# p25rx_display_rev3.net
KiCad netlist of a schematic drawn in EAGLE
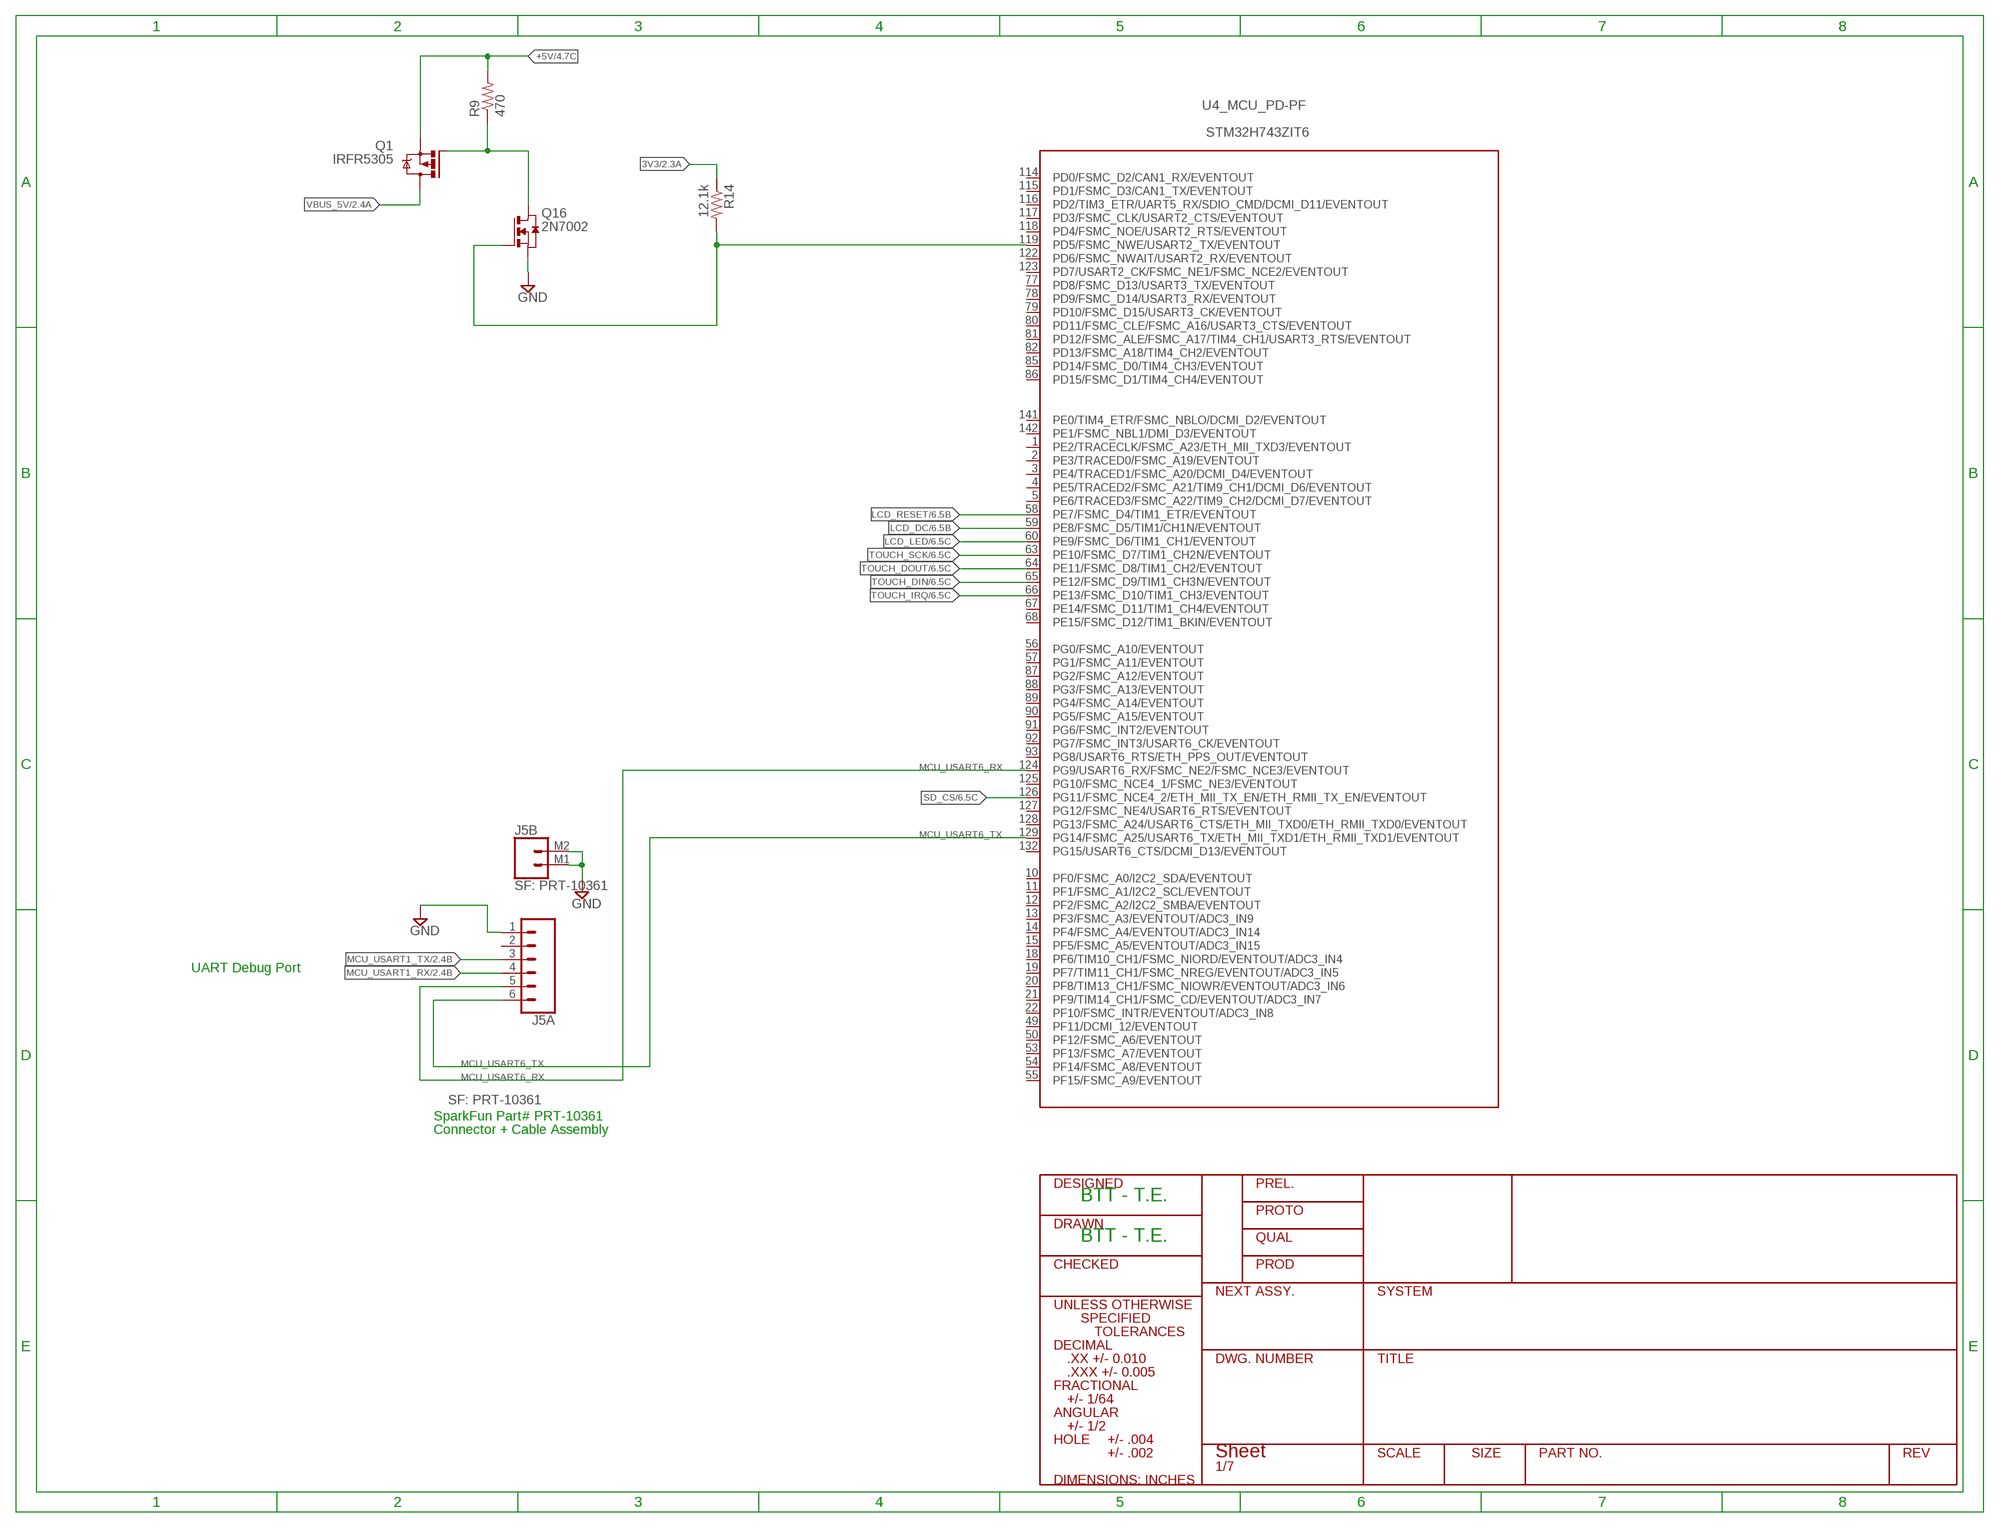
[diagram p0: schematic, sheet 1]
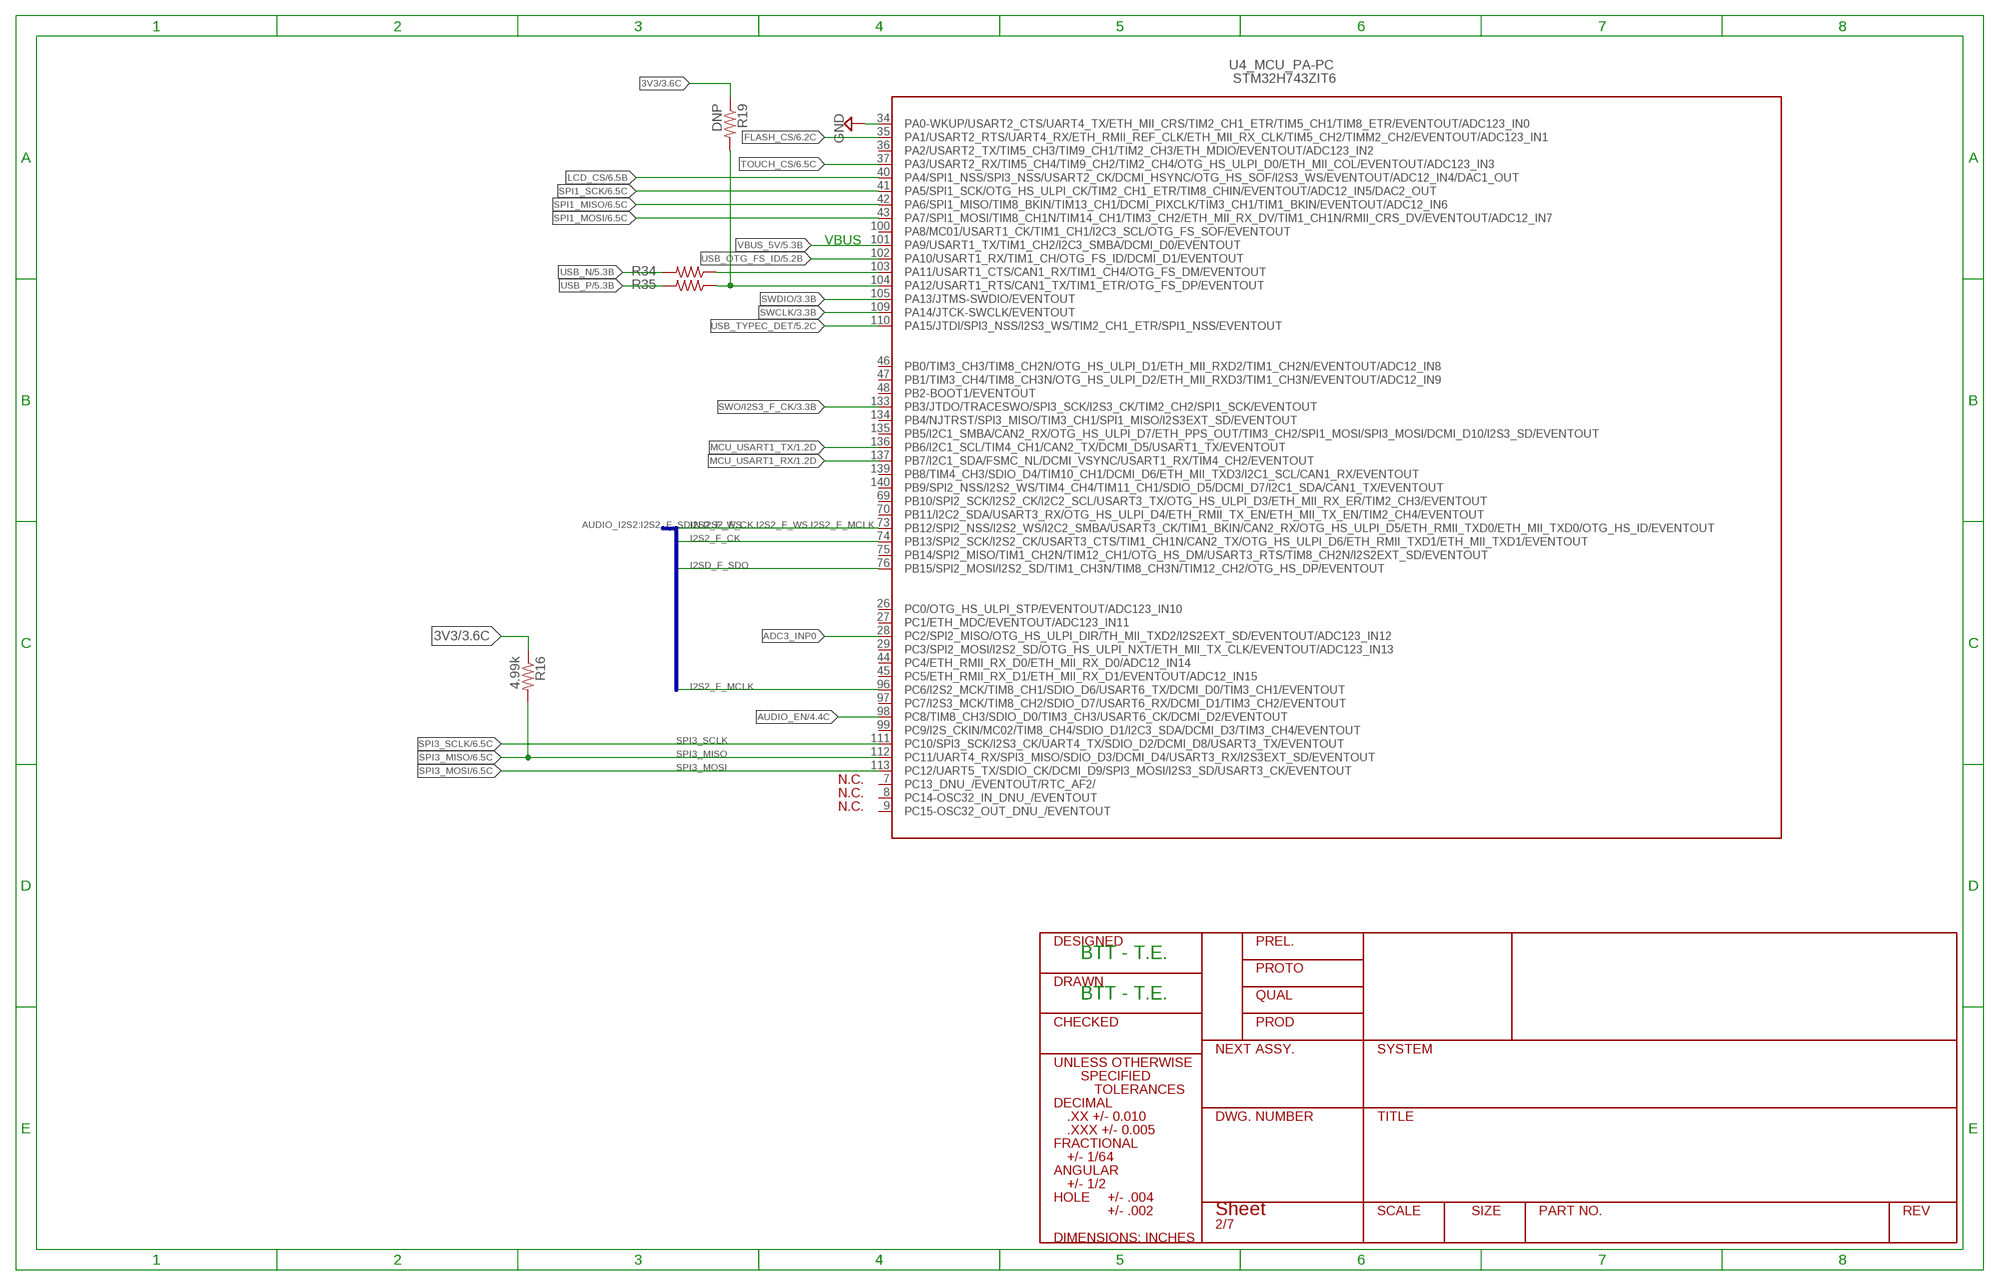
[diagram p1: schematic, sheet 2]
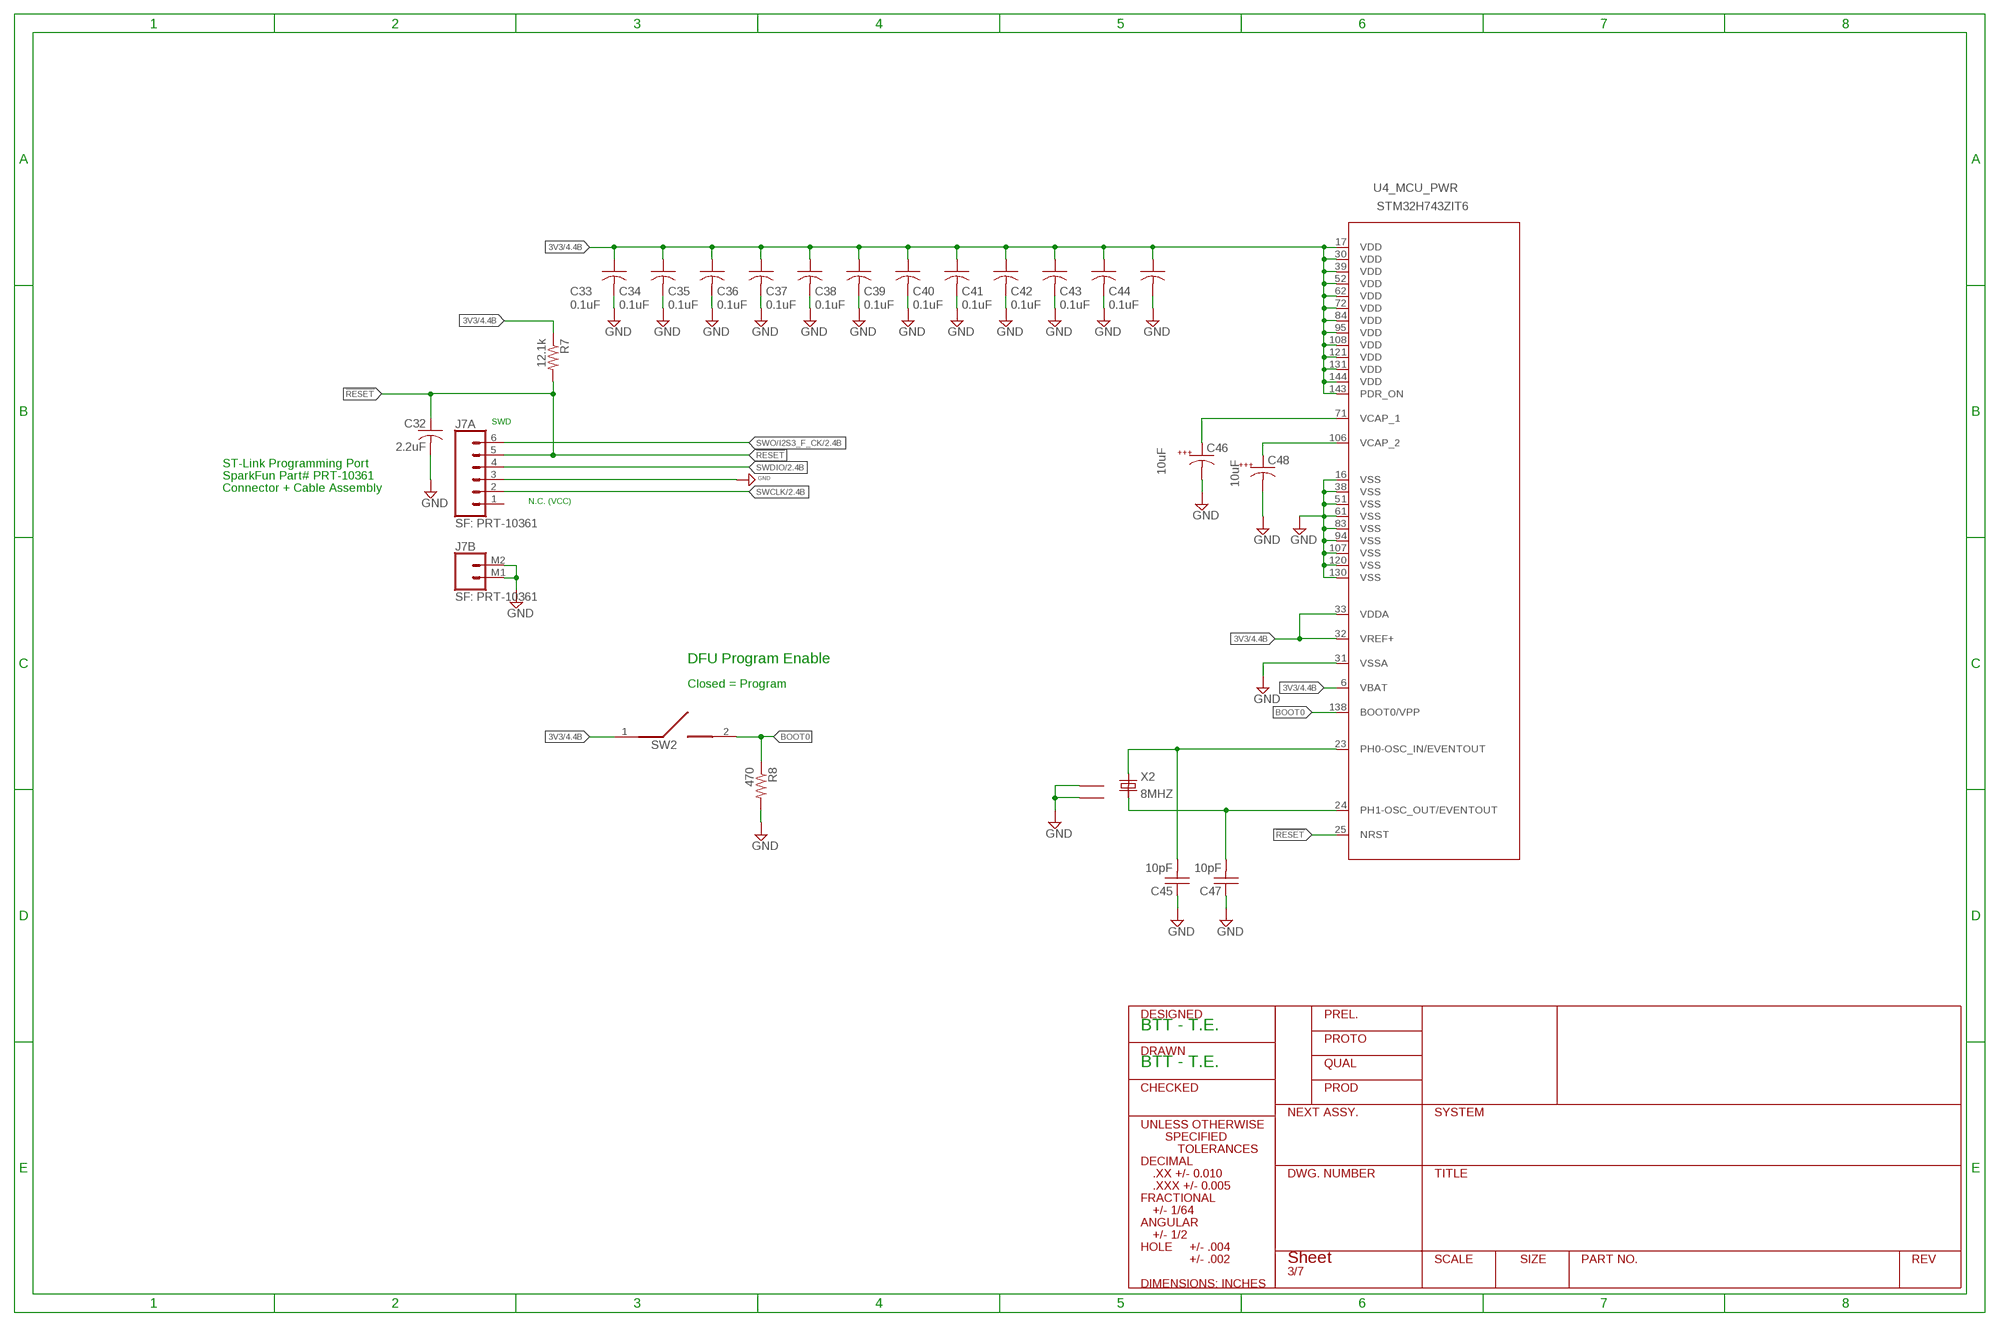
[diagram p2: schematic, sheet 3]
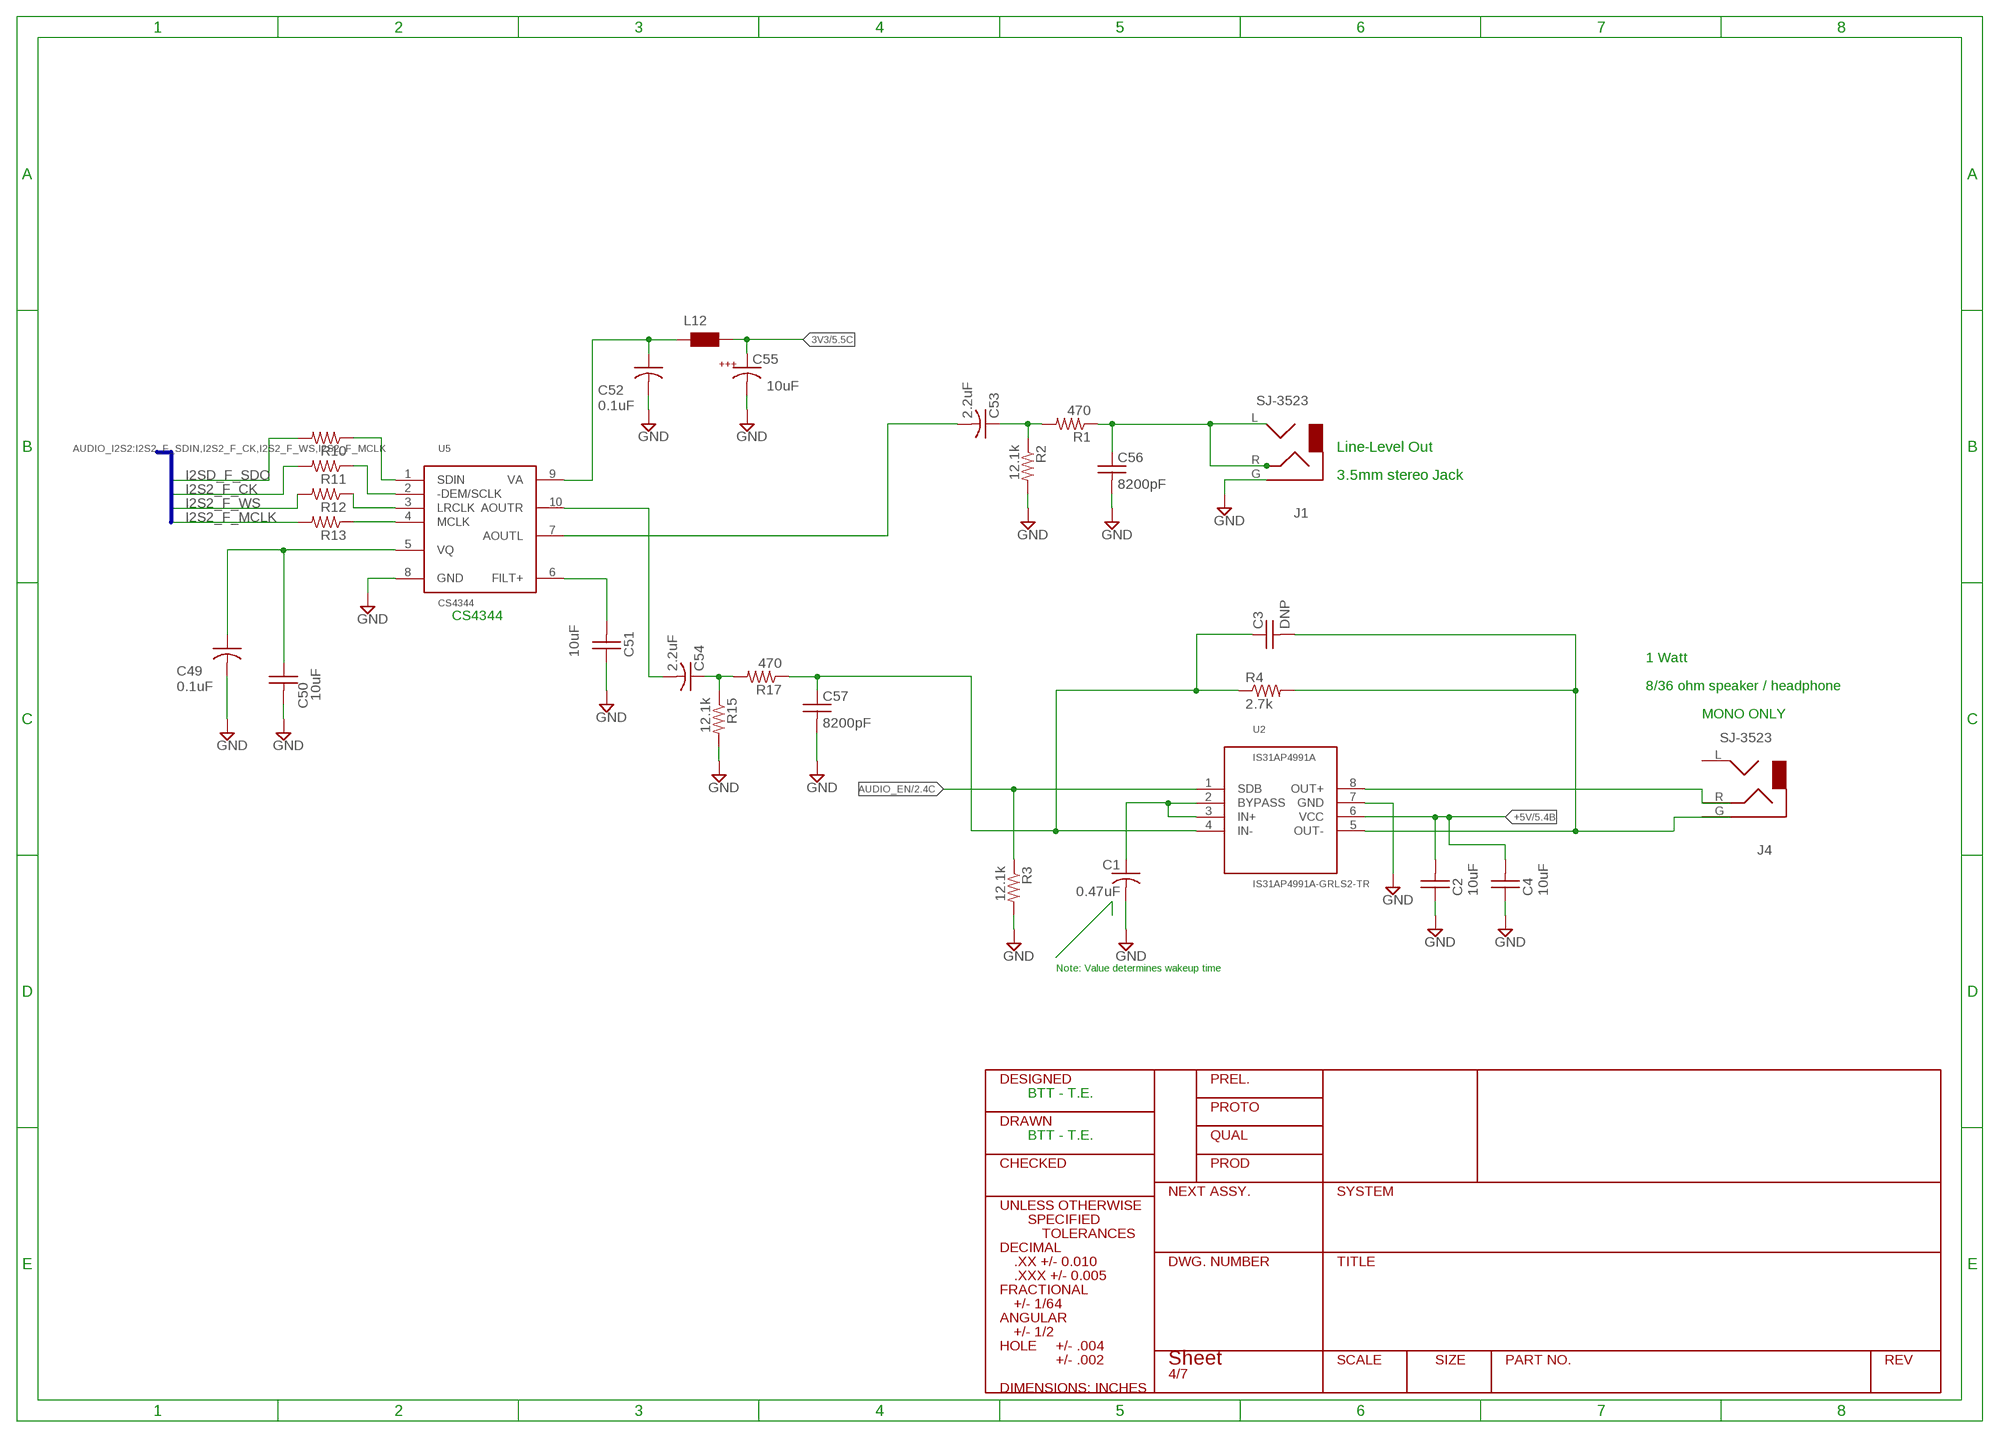
[diagram p3: schematic, sheet 4]
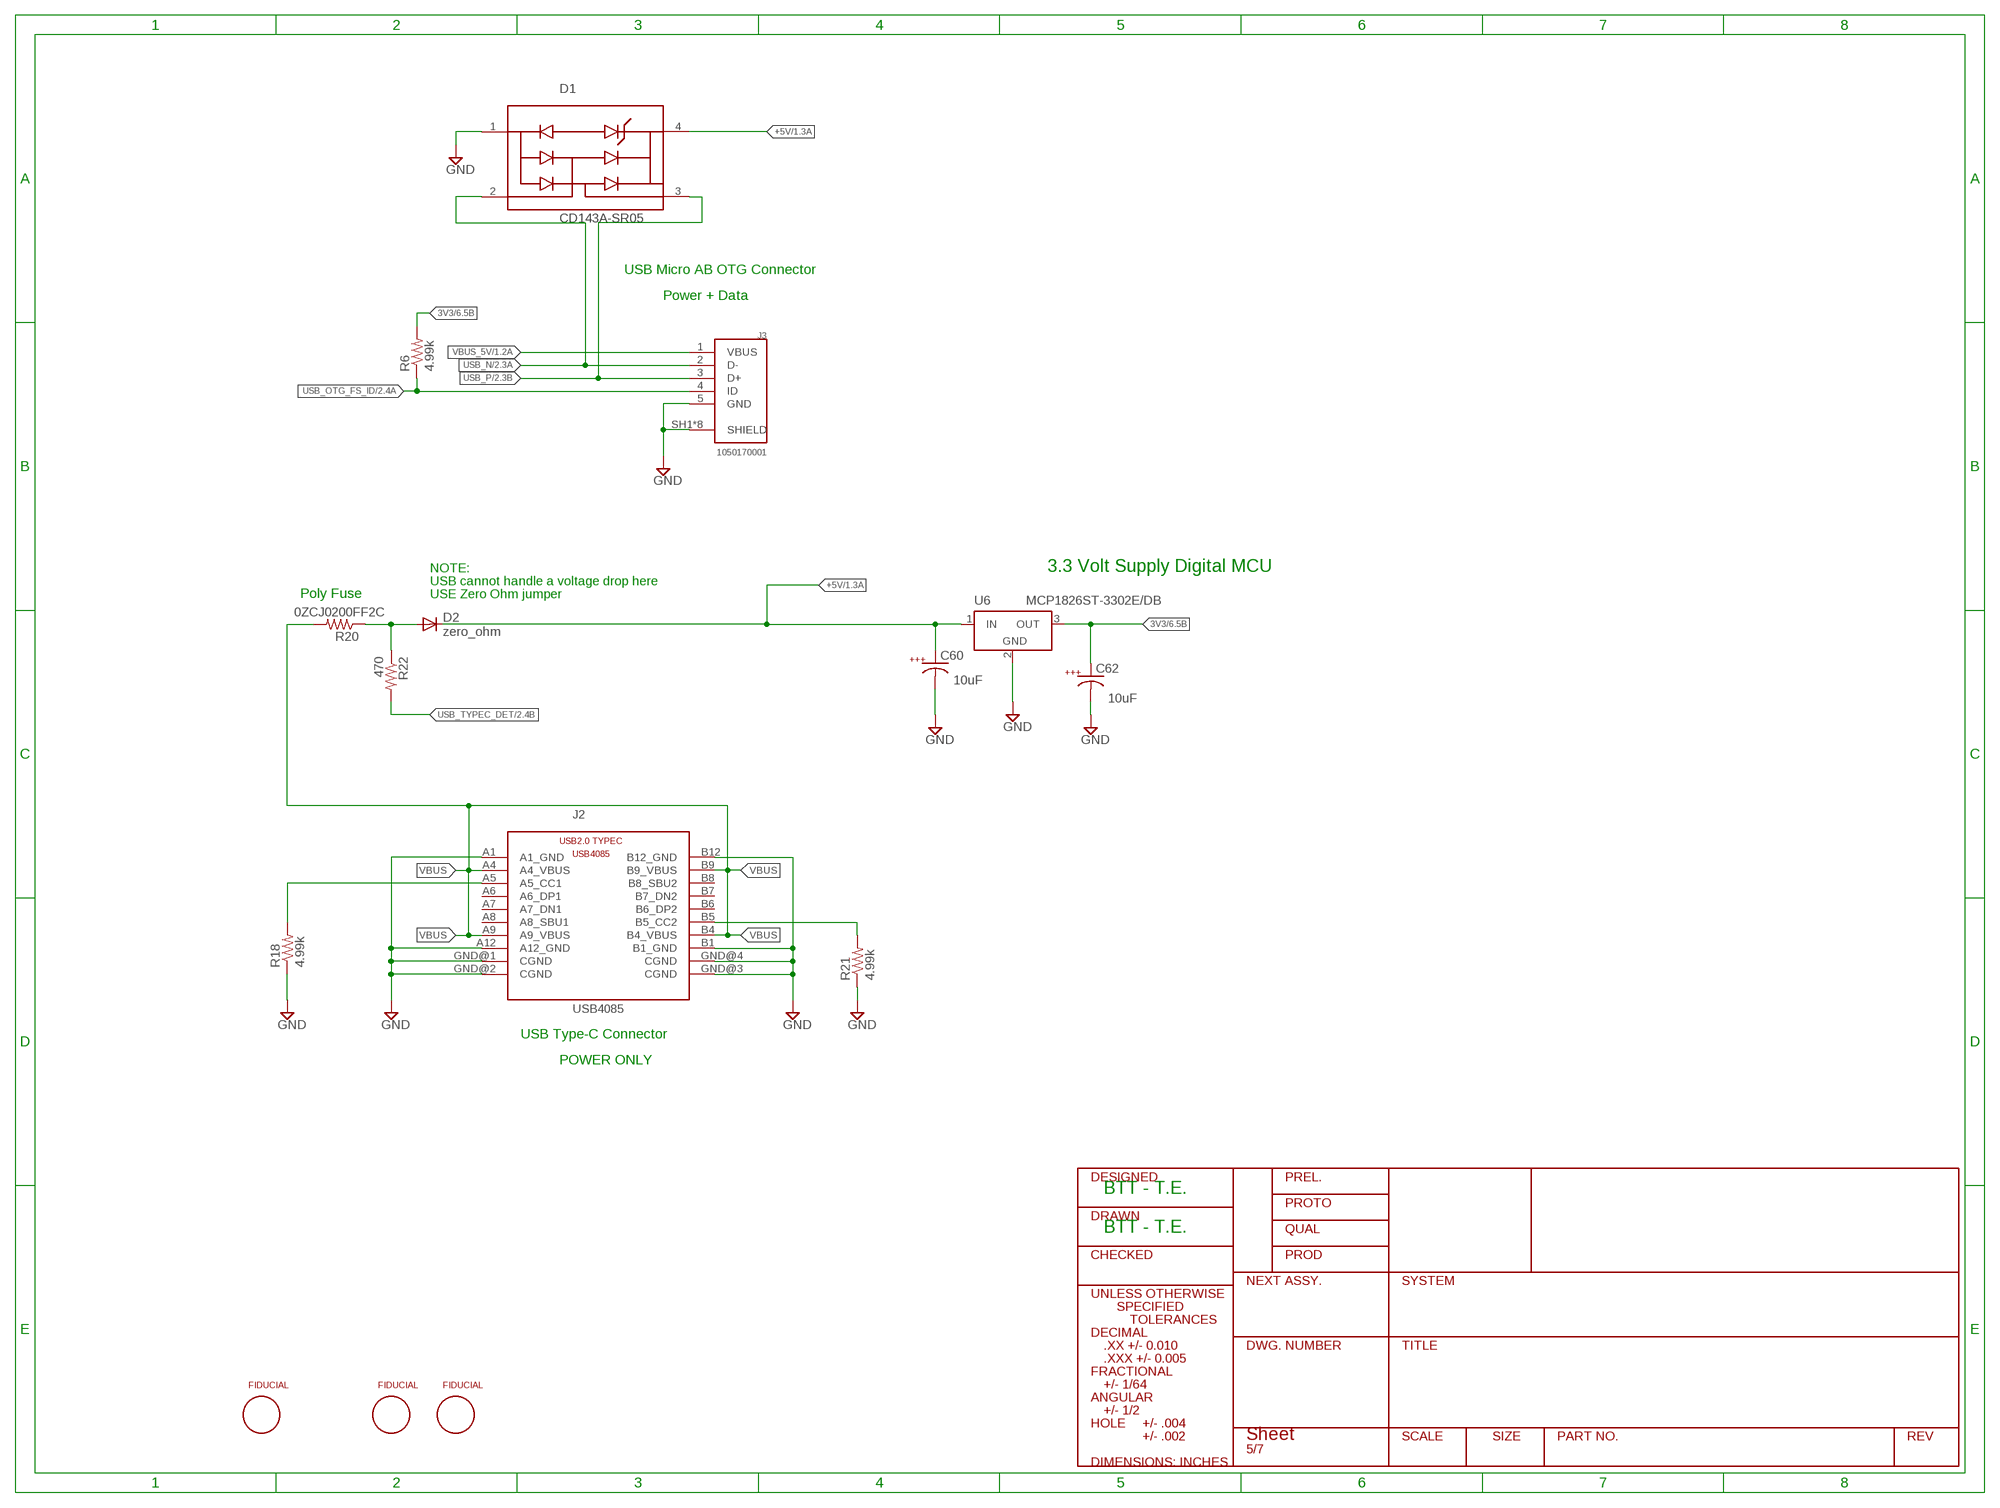
[diagram p4: schematic, sheet 5]
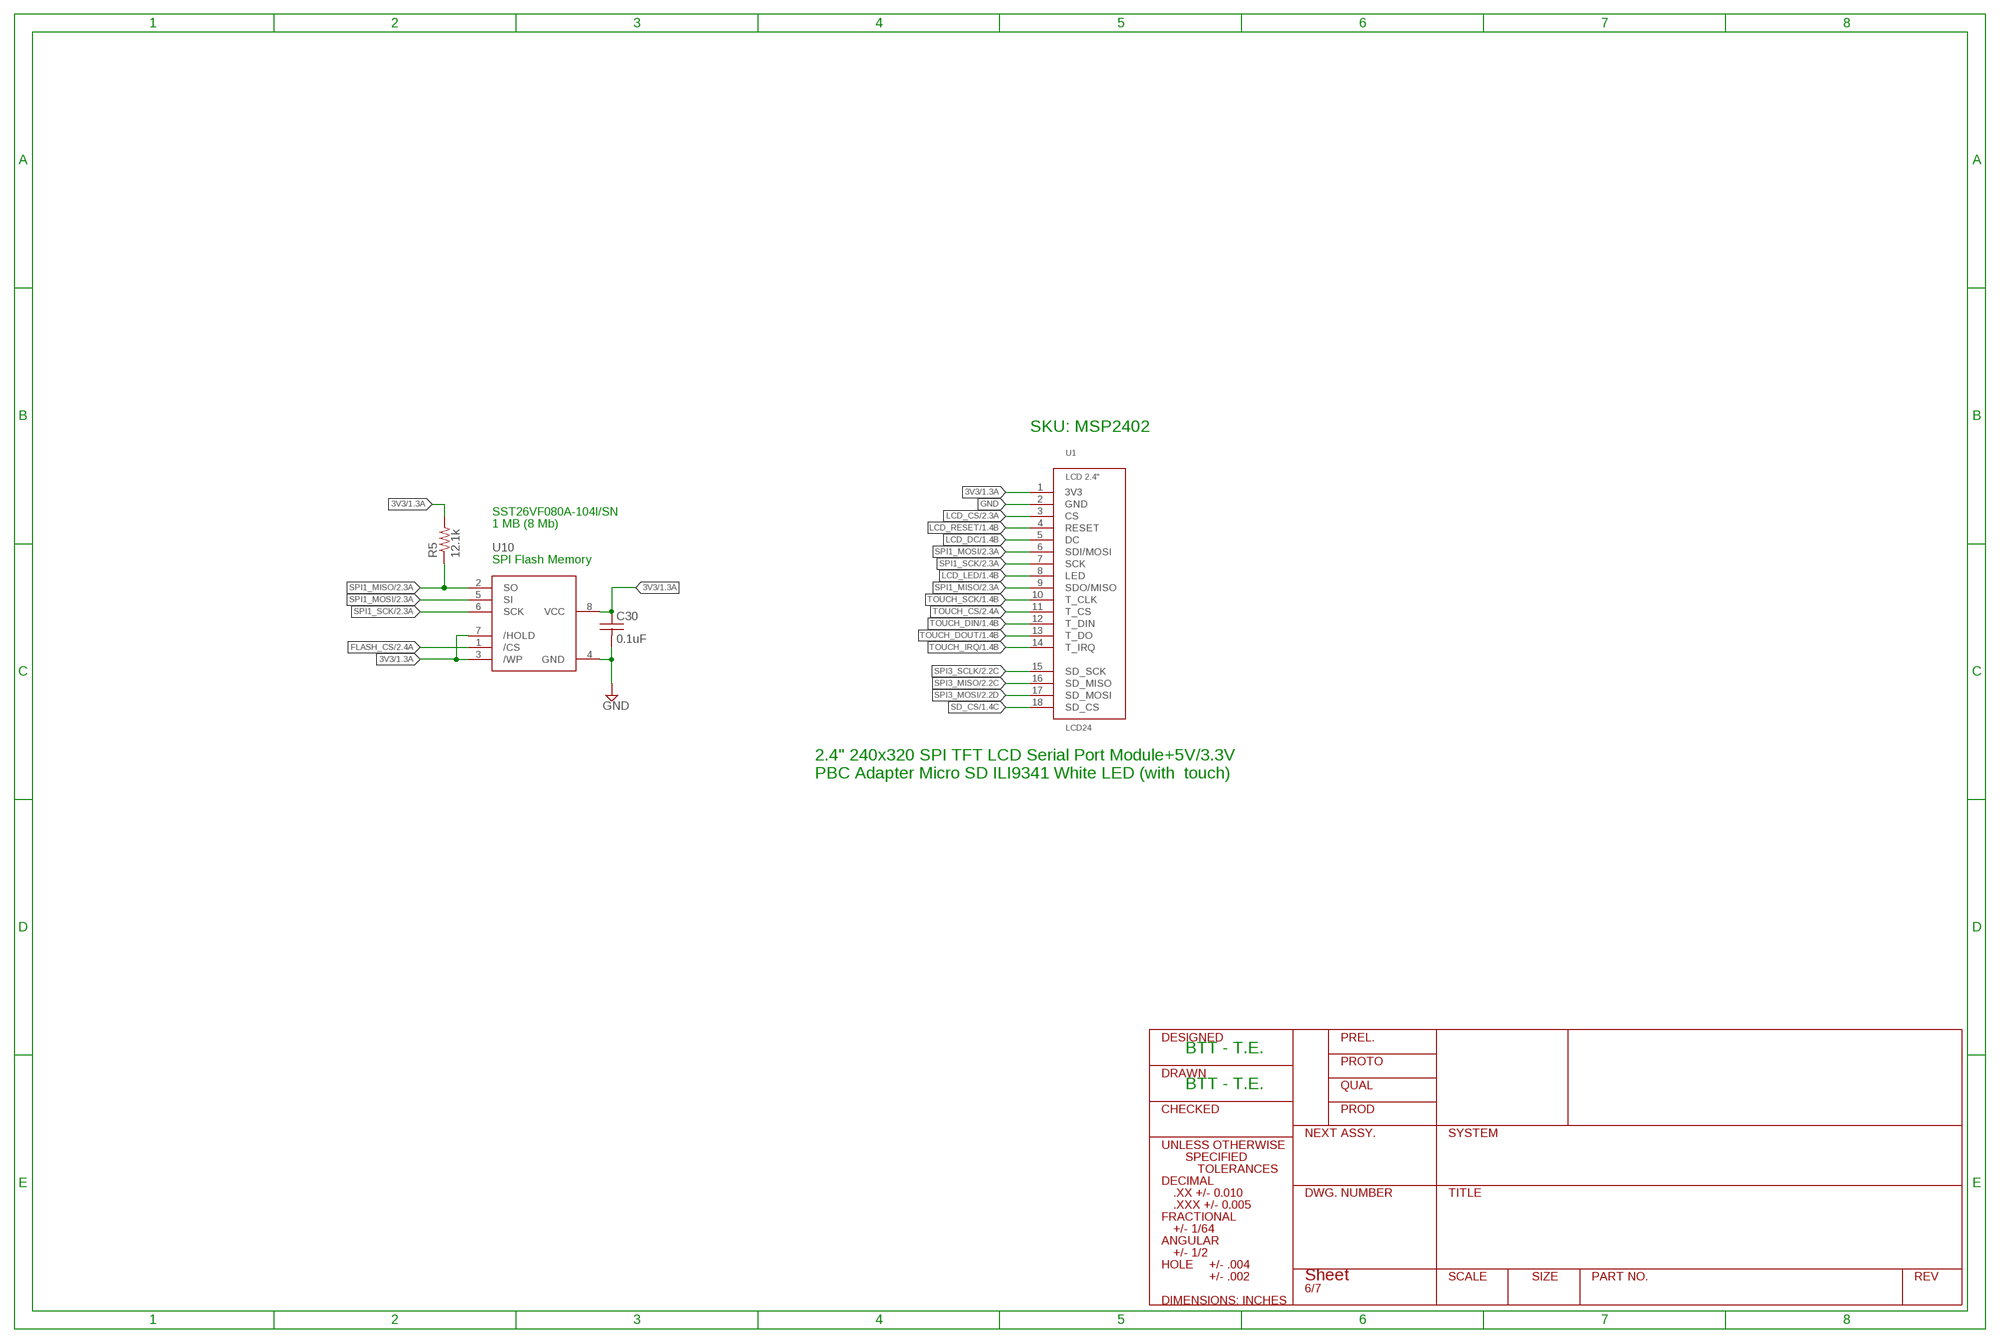
[diagram p5: schematic, sheet 6]
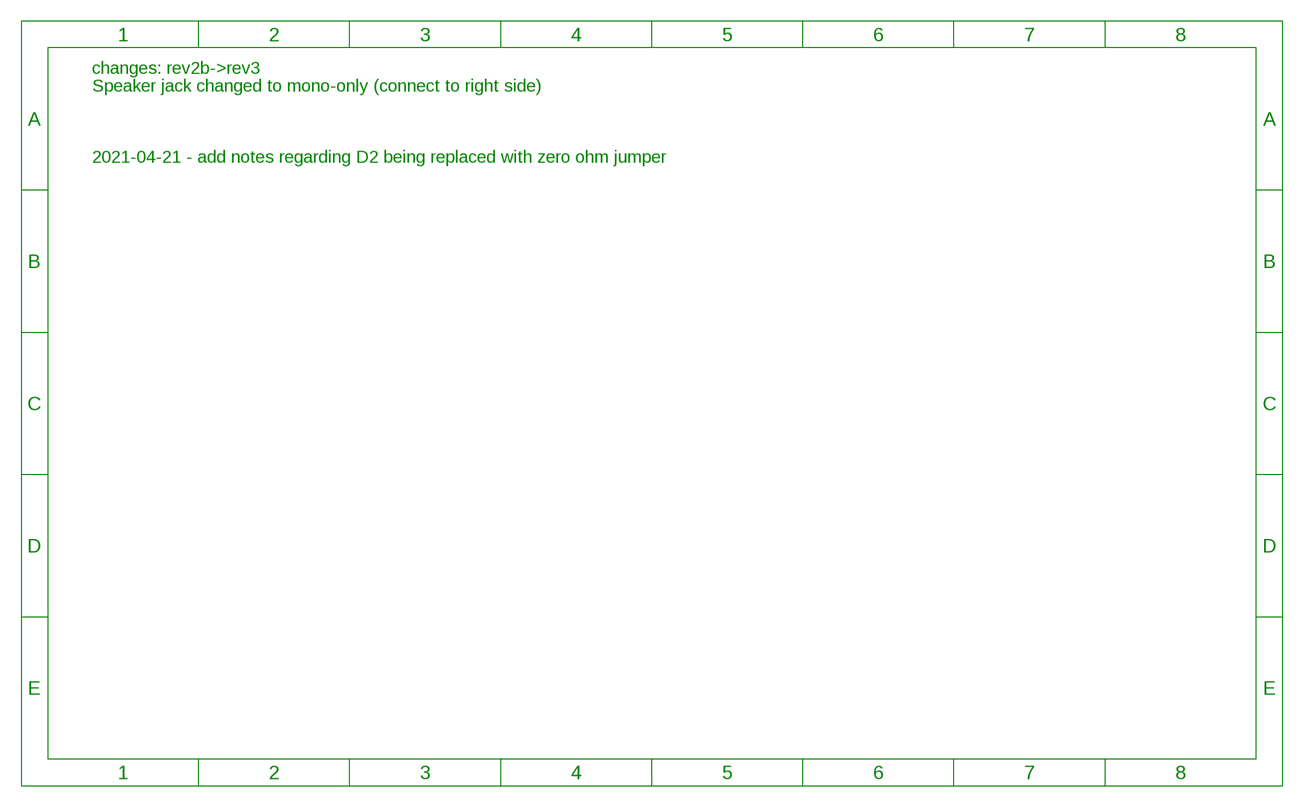
[diagram p6: schematic, sheet 7]

(export (version "E")
  (design (tool "Eeschema 10.0.6"))
  (components
    (comp (ref "C60")
      (value "10uF")
      (footprint "eagle-import:1210K")
      (libsource (lib "eagle-import") (part "CAPACITOR1210K"))
    )
    (comp (ref "C62")
      (value "10uF")
      (footprint "eagle-import:1210K")
      (libsource (lib "eagle-import") (part "CAPACITOR1210K"))
    )
    (comp (ref "D1")
      (value "CD143A-SR05")
      (footprint "eagle-import:SR2.8.TCT_1PRIMARY")
      (libsource (lib "eagle-import") (part "SR2.8_TVS"))
    )
    (comp (ref "D2")
      (value "zero_ohm")
      (footprint "eagle-import:SMB")
      (libsource (lib "eagle-import") (part "DIODE-SMB"))
    )
    (comp (ref "FID1")
      (value "FIDUCIALSMD")
      (footprint "eagle-import:FIDUCIAL")
      (libsource (lib "eagle-import") (part "FIDUCIALSMD"))
    )
    (comp (ref "FID3")
      (value "FIDUCIALSMD")
      (footprint "eagle-import:FIDUCIAL")
      (libsource (lib "eagle-import") (part "FIDUCIALSMD"))
    )
    (comp (ref "FID4")
      (value "FIDUCIALSMD")
      (footprint "eagle-import:FIDUCIAL")
      (libsource (lib "eagle-import") (part "FIDUCIALSMD"))
    )
    (comp (ref "J2")
      (value "USB4085")
      (footprint "eagle-import:GCT_PN_USB4085")
      (libsource (lib "eagle-import") (part "USB4085"))
    )
    (comp (ref "J3")
      (value "1050170001")
      (footprint "eagle-import:MOLEX_1050170001")
      (fields (field (name "DIGI-KEY_PART_NUMBER") "WM1399CT-ND") (field (name "MF") "Molex"))
      (libsource (lib "eagle-import") (part "1050170001"))
    )
    (comp (ref "R6")
      (value "4.99k")
      (footprint "eagle-import:R0402")
      (libsource (lib "eagle-import") (part "R-US_R0402"))
    )
    (comp (ref "R18")
      (value "4.99k")
      (footprint "eagle-import:R0402")
      (libsource (lib "eagle-import") (part "R-US_R0402"))
    )
    (comp (ref "R20")
      (value "0ZCJ0200FF2C")
      (footprint "eagle-import:R1206")
      (libsource (lib "eagle-import") (part "R-US_R1206"))
    )
    (comp (ref "R21")
      (value "4.99k")
      (footprint "eagle-import:R0402")
      (libsource (lib "eagle-import") (part "R-US_R0402"))
    )
    (comp (ref "R22")
      (value "470")
      (footprint "eagle-import:R0402")
      (libsource (lib "eagle-import") (part "misclib3_R-US_R0402"))
    )
    (comp (ref "U6")
      (value "MCP1826ST-3302E/DB")
      (footprint "eagle-import:SOT223")
      (fields (field (name "MPN") "LT1129CST-5#PBF"))
      (libsource (lib "eagle-import") (part "LT1129CST5"))
    )
    (comp (ref "C32")
      (value "2.2uF")
      (footprint "eagle-import:C0805")
      (libsource (lib "eagle-import") (part "resistor_C-USC0805"))
    )
    (comp (ref "C33")
      (value "0.1uF")
      (footprint "eagle-import:0402")
      (libsource (lib "eagle-import") (part "misclib4_CAPACITOR0402"))
    )
    (comp (ref "C34")
      (value "0.1uF")
      (footprint "eagle-import:0402")
      (libsource (lib "eagle-import") (part "misclib4_CAPACITOR0402"))
    )
    (comp (ref "C35")
      (value "0.1uF")
      (footprint "eagle-import:0402")
      (libsource (lib "eagle-import") (part "misclib4_CAPACITOR0402"))
    )
    (comp (ref "C36")
      (value "0.1uF")
      (footprint "eagle-import:0402")
      (libsource (lib "eagle-import") (part "misclib4_CAPACITOR0402"))
    )
    (comp (ref "C37")
      (value "0.1uF")
      (footprint "eagle-import:0402")
      (libsource (lib "eagle-import") (part "misclib4_CAPACITOR0402"))
    )
    (comp (ref "C38")
      (value "0.1uF")
      (footprint "eagle-import:0402")
      (libsource (lib "eagle-import") (part "misclib4_CAPACITOR0402"))
    )
    (comp (ref "C39")
      (value "0.1uF")
      (footprint "eagle-import:0402")
      (libsource (lib "eagle-import") (part "misclib4_CAPACITOR0402"))
    )
    (comp (ref "C40")
      (value "0.1uF")
      (footprint "eagle-import:0402")
      (libsource (lib "eagle-import") (part "misclib4_CAPACITOR0402"))
    )
    (comp (ref "C41")
      (value "0.1uF")
      (footprint "eagle-import:0402")
      (libsource (lib "eagle-import") (part "misclib4_CAPACITOR0402"))
    )
    (comp (ref "C42")
      (value "0.1uF")
      (footprint "eagle-import:0402")
      (libsource (lib "eagle-import") (part "misclib4_CAPACITOR0402"))
    )
    (comp (ref "C43")
      (value "0.1uF")
      (footprint "eagle-import:0402")
      (libsource (lib "eagle-import") (part "misclib4_CAPACITOR0402"))
    )
    (comp (ref "C44")
      (value "0.1uF")
      (footprint "eagle-import:0402")
      (libsource (lib "eagle-import") (part "misclib4_CAPACITOR0402"))
    )
    (comp (ref "C45")
      (value "10pF")
      (footprint "eagle-import:C0603")
      (libsource (lib "eagle-import") (part "misc6_C-USC0603"))
    )
    (comp (ref "C46")
      (value "10uF")
      (footprint "eagle-import:1210K")
      (libsource (lib "eagle-import") (part "CAPACITOR1210K"))
    )
    (comp (ref "C47")
      (value "10pF")
      (footprint "eagle-import:C0603")
      (libsource (lib "eagle-import") (part "misc6_C-USC0603"))
    )
    (comp (ref "C48")
      (value "10uF")
      (footprint "eagle-import:1210K")
      (libsource (lib "eagle-import") (part "CAPACITOR1210K"))
    )
    (comp (ref "J7")
      (value "SF: PRT-10361")
      (footprint "eagle-import:JST-6-SMD-HORI-1.0MM")
      (libsource (lib "eagle-import") (part "JST_6_PIN_HORIZONTAL"))
    )
    (comp (ref "R7")
      (value "12.1k")
      (footprint "eagle-import:R0603")
      (libsource (lib "eagle-import") (part "R-US_R0603"))
    )
    (comp (ref "R8")
      (value "470")
      (footprint "eagle-import:R0402")
      (libsource (lib "eagle-import") (part "misclib3_R-US_R0402"))
    )
    (comp (ref "SW2")
      (value "CHS-01TA")
      (footprint "eagle-import:CHS1BIT")
      (libsource (lib "eagle-import") (part "CHS-01TA"))
    )
    (comp (ref "U4")
      (value "STM32H743ZIT6")
      (footprint "eagle-import:STM32F407_144")
      (libsource (lib "eagle-import") (part "STM32F407_144_MG144"))
    )
    (comp (ref "X2")
      (value "8MHZ")
      (footprint "eagle-import:ECS-250-20-30B-DU_CRYSTAL")
      (libsource (lib "eagle-import") (part "ECS-250-20-30B-DUDU"))
    )
    (comp (ref "R16")
      (value "4.99k")
      (footprint "eagle-import:R0402")
      (libsource (lib "eagle-import") (part "misclib3_R-US_R0402"))
    )
    (comp (ref "R19")
      (value "DNP")
      (footprint "eagle-import:R0603")
      (libsource (lib "eagle-import") (part "R-US_R0603"))
    )
    (comp (ref "R34")
      (value "470")
      (footprint "eagle-import:R0402")
      (libsource (lib "eagle-import") (part "misclib3_R-US_R0402"))
    )
    (comp (ref "R35")
      (value "470")
      (footprint "eagle-import:R0402")
      (libsource (lib "eagle-import") (part "misclib3_R-US_R0402"))
    )
    (comp (ref "J5")
      (value "SF: PRT-10361")
      (footprint "eagle-import:JST-6-SMD-HORI-1.0MM")
      (libsource (lib "eagle-import") (part "JST_6_PIN_HORIZONTAL"))
    )
    (comp (ref "Q1")
      (value "IRFR5305")
      (footprint "eagle-import:D-PAK_TO252AA")
      (libsource (lib "eagle-import") (part "IRF?5305R"))
    )
    (comp (ref "Q16")
      (value "2N7002")
      (footprint "eagle-import:SOT23_2N7002_PACKAGE")
      (libsource (lib "eagle-import") (part "2N7002"))
    )
    (comp (ref "R9")
      (value "470")
      (footprint "eagle-import:R0603")
      (libsource (lib "eagle-import") (part "R-US_R0603"))
    )
    (comp (ref "R14")
      (value "12.1k")
      (footprint "eagle-import:R0402")
      (libsource (lib "eagle-import") (part "misclib3_R-US_R0402"))
    )
    (comp (ref "C1")
      (value "0.47uF")
      (footprint "eagle-import:C0805")
      (libsource (lib "eagle-import") (part "resistor_C-USC0805"))
    )
    (comp (ref "C2")
      (value "10uF")
      (footprint "eagle-import:C0805")
      (libsource (lib "eagle-import") (part "misclib3_C-USC0805"))
    )
    (comp (ref "C3")
      (value "DNP")
      (footprint "eagle-import:C0603")
      (libsource (lib "eagle-import") (part "misclib3_C-USC0603"))
    )
    (comp (ref "C4")
      (value "10uF")
      (footprint "eagle-import:C0805")
      (libsource (lib "eagle-import") (part "misclib3_C-USC0805"))
    )
    (comp (ref "C49")
      (value "0.1uF")
      (footprint "eagle-import:0402")
      (libsource (lib "eagle-import") (part "misclib4_CAPACITOR0402"))
    )
    (comp (ref "C50")
      (value "10uF")
      (footprint "eagle-import:C0805")
      (libsource (lib "eagle-import") (part "misclib3_C-USC0805"))
    )
    (comp (ref "C51")
      (value "10uF")
      (footprint "eagle-import:C0805")
      (libsource (lib "eagle-import") (part "misclib3_C-USC0805"))
    )
    (comp (ref "C52")
      (value "0.1uF")
      (footprint "eagle-import:0402")
      (libsource (lib "eagle-import") (part "misclib4_CAPACITOR0402"))
    )
    (comp (ref "C53")
      (value "2.2uF")
      (footprint "eagle-import:C0805")
      (libsource (lib "eagle-import") (part "resistor_C-USC0805"))
    )
    (comp (ref "C54")
      (value "2.2uF")
      (footprint "eagle-import:C0805")
      (libsource (lib "eagle-import") (part "resistor_C-USC0805"))
    )
    (comp (ref "C55")
      (value "10uF")
      (footprint "eagle-import:1210K")
      (libsource (lib "eagle-import") (part "CAPACITOR1210K"))
    )
    (comp (ref "C56")
      (value "8200pF")
      (footprint "eagle-import:C0603")
      (libsource (lib "eagle-import") (part "misclib3_C-USC0603"))
    )
    (comp (ref "C57")
      (value "8200pF")
      (footprint "eagle-import:C0603")
      (libsource (lib "eagle-import") (part "misclib3_C-USC0603"))
    )
    (comp (ref "J1")
      (value "SJ-3523")
      (footprint "eagle-import:SJ-3523")
      (libsource (lib "eagle-import") (part "CUI_SJ-3523SMT"))
    )
    (comp (ref "J4")
      (value "SJ-3523")
      (footprint "eagle-import:SJ-3523")
      (libsource (lib "eagle-import") (part "CUI_SJ-3523SMT"))
    )
    (comp (ref "L12")
      (value "WE-CBF_0603")
      (footprint "eagle-import:0603")
      (libsource (lib "eagle-import") (part "WE-CBF_0603"))
    )
    (comp (ref "R1")
      (value "470")
      (footprint "eagle-import:R0402")
      (libsource (lib "eagle-import") (part "misclib3_R-US_R0402"))
    )
    (comp (ref "R2")
      (value "12.1k")
      (footprint "eagle-import:R0603")
      (libsource (lib "eagle-import") (part "R-US_R0603"))
    )
    (comp (ref "R3")
      (value "12.1k")
      (footprint "eagle-import:R0603")
      (libsource (lib "eagle-import") (part "R-US_R0603"))
    )
    (comp (ref "R4")
      (value "2.7k")
      (footprint "eagle-import:R0603")
      (libsource (lib "eagle-import") (part "R-US_R0603"))
    )
    (comp (ref "R10")
      (value "470")
      (footprint "eagle-import:R0402")
      (libsource (lib "eagle-import") (part "misclib3_R-US_R0402"))
    )
    (comp (ref "R11")
      (value "470")
      (footprint "eagle-import:R0402")
      (libsource (lib "eagle-import") (part "misclib3_R-US_R0402"))
    )
    (comp (ref "R12")
      (value "470")
      (footprint "eagle-import:R0402")
      (libsource (lib "eagle-import") (part "misclib3_R-US_R0402"))
    )
    (comp (ref "R13")
      (value "470")
      (footprint "eagle-import:R0402")
      (libsource (lib "eagle-import") (part "misclib3_R-US_R0402"))
    )
    (comp (ref "R15")
      (value "12.1k")
      (footprint "eagle-import:R0603")
      (libsource (lib "eagle-import") (part "R-US_R0603"))
    )
    (comp (ref "R17")
      (value "470")
      (footprint "eagle-import:R0402")
      (libsource (lib "eagle-import") (part "misclib3_R-US_R0402"))
    )
    (comp (ref "U2")
      (value "IS31AP4991A-GRLS2-TR")
      (footprint "eagle-import:SO8")
      (libsource (lib "eagle-import") (part "IS31AP4991A-GRLS2-TR"))
    )
    (comp (ref "U5")
      (value "CS4344")
      (footprint "eagle-import:MSOP10")
      (libsource (lib "eagle-import") (part "CS4344"))
    )
    (comp (ref "C30")
      (value "0.1uF")
      (footprint "eagle-import:C0402")
      (libsource (lib "eagle-import") (part "C-USC0402"))
    )
    (comp (ref "R5")
      (value "12.1k")
      (footprint "eagle-import:R0603")
      (libsource (lib "eagle-import") (part "R-US_R0603"))
    )
    (comp (ref "U1")
      (value "LCD24")
      (footprint "eagle-import:LCD_24")
      (libsource (lib "eagle-import") (part "LCD24"))
    )
    (comp (ref "U10")
      (value "AT25F512ASOIC")
      (footprint "eagle-import:SO8")
      (libsource (lib "eagle-import") (part "AT25F512ASOIC"))
    )
  )
  (nets
    (net (code "3") (name "+5V") (class "Default")
      (node (ref "C2") (pin "2") (pinfunction "2_2") (pintype "passive"))
      (node (ref "C4") (pin "2") (pinfunction "2_2") (pintype "passive"))
      (node (ref "C60") (pin "A") (pinfunction "A_A") (pintype "passive"))
      (node (ref "D1") (pin "4") (pinfunction "REF_4") (pintype "passive"))
      (node (ref "D2") (pin "C") (pinfunction "C_C") (pintype "passive"))
      (node (ref "Q1") (pin "3") (pinfunction "S_3") (pintype "passive"))
      (node (ref "R9") (pin "2") (pinfunction "2_2") (pintype "passive"))
      (node (ref "U2") (pin "6") (pinfunction "VCC_6") (pintype "passive"))
      (node (ref "U6") (pin "1") (pinfunction "IN_1") (pintype "input"))
    )
    (net (code "6") (name "3V3") (class "Default")
      (node (ref "C30") (pin "1") (pinfunction "1_1") (pintype "passive"))
      (node (ref "C33") (pin "1") (pinfunction "A_1") (pintype "passive"))
      (node (ref "C34") (pin "1") (pinfunction "A_1") (pintype "passive"))
      (node (ref "C35") (pin "1") (pinfunction "A_1") (pintype "passive"))
      (node (ref "C36") (pin "1") (pinfunction "A_1") (pintype "passive"))
      (node (ref "C37") (pin "1") (pinfunction "A_1") (pintype "passive"))
      (node (ref "C38") (pin "1") (pinfunction "A_1") (pintype "passive"))
      (node (ref "C39") (pin "1") (pinfunction "A_1") (pintype "passive"))
      (node (ref "C40") (pin "1") (pinfunction "A_1") (pintype "passive"))
      (node (ref "C41") (pin "1") (pinfunction "A_1") (pintype "passive"))
      (node (ref "C42") (pin "1") (pinfunction "A_1") (pintype "passive"))
      (node (ref "C43") (pin "1") (pinfunction "A_1") (pintype "passive"))
      (node (ref "C44") (pin "1") (pinfunction "A_1") (pintype "passive"))
      (node (ref "C55") (pin "A") (pinfunction "A_A") (pintype "passive"))
      (node (ref "C62") (pin "A") (pinfunction "A_A") (pintype "passive"))
      (node (ref "L12") (pin "2") (pinfunction "2_2") (pintype "passive"))
      (node (ref "R14") (pin "1") (pinfunction "1_1") (pintype "passive"))
      (node (ref "R16") (pin "1") (pinfunction "1_1") (pintype "passive"))
      (node (ref "R19") (pin "1") (pinfunction "1_1") (pintype "passive"))
      (node (ref "R5") (pin "2") (pinfunction "2_2") (pintype "passive"))
      (node (ref "R6") (pin "2") (pinfunction "2_2") (pintype "passive"))
      (node (ref "R7") (pin "1") (pinfunction "1_1") (pintype "passive"))
      (node (ref "SW2") (pin "1") (pinfunction "P$1_1") (pintype "passive"))
      (node (ref "U1") (pin "1") (pinfunction "3V3_1") (pintype "passive"))
      (node (ref "U10") (pin "3") (pinfunction "/WP_3") (pintype "input"))
      (node (ref "U10") (pin "7") (pinfunction "/HOLD_7") (pintype "input"))
      (node (ref "U10") (pin "8") (pinfunction "VCC_8") (pintype "power_in"))
      (node (ref "U4") (pin "108") (pinfunction "VDD_108") (pintype "passive"))
      (node (ref "U4") (pin "121") (pinfunction "VDD_121") (pintype "passive"))
      (node (ref "U4") (pin "131") (pinfunction "VDD_131") (pintype "passive"))
      (node (ref "U4") (pin "143") (pinfunction "PDR_ON_143") (pintype "passive"))
      (node (ref "U4") (pin "144") (pinfunction "VDD_144") (pintype "passive"))
      (node (ref "U4") (pin "17") (pinfunction "VDD_17") (pintype "passive"))
      (node (ref "U4") (pin "30") (pinfunction "VDD_30") (pintype "passive"))
      (node (ref "U4") (pin "32") (pinfunction "VREF+_32") (pintype "passive"))
      (node (ref "U4") (pin "33") (pinfunction "VDDA_33") (pintype "passive"))
      (node (ref "U4") (pin "39") (pinfunction "VDD_39") (pintype "passive"))
      (node (ref "U4") (pin "52") (pinfunction "VDD_52") (pintype "passive"))
      (node (ref "U4") (pin "6") (pinfunction "VBAT_6") (pintype "passive"))
      (node (ref "U4") (pin "62") (pinfunction "VDD_62") (pintype "passive"))
      (node (ref "U4") (pin "72") (pinfunction "VDD_72") (pintype "passive"))
      (node (ref "U4") (pin "84") (pinfunction "VDD_84") (pintype "passive"))
      (node (ref "U4") (pin "95") (pinfunction "VDD_95") (pintype "passive"))
      (node (ref "U6") (pin "3") (pinfunction "OUT_3") (pintype "output"))
    )
    (net (code "7") (name "ADC3_INP0") (class "Default")
      (node (ref "U4") (pin "28") (pinfunction "PC2/SPI2_MISO/OTG_HS_ULPI_DIR/TH_MII_TXD2/I2S2EXT_SD/EVENTOUT/ADC123_IN12_28") (pintype "passive"))
    )
    (net (code "8") (name "AUDIO_EN") (class "Default")
      (node (ref "R3") (pin "1") (pinfunction "1_1") (pintype "passive"))
      (node (ref "U2") (pin "1") (pinfunction "SDB_1") (pintype "passive"))
      (node (ref "U4") (pin "98") (pinfunction "PC8/TIM8_CH3/SDIO_D0/TIM3_CH3/USART6_CK/DCMI_D2/EVENTOUT_98") (pintype "passive"))
    )
    (net (code "9") (name "BOOT0") (class "Default")
      (node (ref "R8") (pin "1") (pinfunction "1_1") (pintype "passive"))
      (node (ref "SW2") (pin "2") (pinfunction "P$2_2") (pintype "passive"))
      (node (ref "U4") (pin "138") (pinfunction "BOOT0/VPP_138") (pintype "passive"))
    )
    (net (code "10") (name "FLASH_CS") (class "Default")
      (node (ref "U10") (pin "1") (pinfunction "/CS_1") (pintype "input"))
      (node (ref "U4") (pin "35") (pinfunction "PA1/USART2_RTS/UART4_RX/ETH_RMII_REF_CLK/ETH_MII_RX_CLK/TIM5_CH2/TIMM2_CH2/EVENTOUT/ADC123_IN1_35") (pintype "passive"))
    )
    (net (code "11") (name "GND") (class "Default")
      (node (ref "C1") (pin "2") (pinfunction "2_2") (pintype "passive"))
      (node (ref "C2") (pin "1") (pinfunction "1_1") (pintype "passive"))
      (node (ref "C30") (pin "2") (pinfunction "2_2") (pintype "passive"))
      (node (ref "C32") (pin "2") (pinfunction "2_2") (pintype "passive"))
      (node (ref "C33") (pin "2") (pinfunction "C_2") (pintype "passive"))
      (node (ref "C34") (pin "2") (pinfunction "C_2") (pintype "passive"))
      (node (ref "C35") (pin "2") (pinfunction "C_2") (pintype "passive"))
      (node (ref "C36") (pin "2") (pinfunction "C_2") (pintype "passive"))
      (node (ref "C37") (pin "2") (pinfunction "C_2") (pintype "passive"))
      (node (ref "C38") (pin "2") (pinfunction "C_2") (pintype "passive"))
      (node (ref "C39") (pin "2") (pinfunction "C_2") (pintype "passive"))
      (node (ref "C4") (pin "1") (pinfunction "1_1") (pintype "passive"))
      (node (ref "C40") (pin "2") (pinfunction "C_2") (pintype "passive"))
      (node (ref "C41") (pin "2") (pinfunction "C_2") (pintype "passive"))
      (node (ref "C42") (pin "2") (pinfunction "C_2") (pintype "passive"))
      (node (ref "C43") (pin "2") (pinfunction "C_2") (pintype "passive"))
      (node (ref "C44") (pin "2") (pinfunction "C_2") (pintype "passive"))
      (node (ref "C45") (pin "1") (pinfunction "1_1") (pintype "passive"))
      (node (ref "C46") (pin "C") (pinfunction "C_C") (pintype "passive"))
      (node (ref "C47") (pin "1") (pinfunction "1_1") (pintype "passive"))
      (node (ref "C48") (pin "C") (pinfunction "C_C") (pintype "passive"))
      (node (ref "C49") (pin "2") (pinfunction "C_2") (pintype "passive"))
      (node (ref "C50") (pin "2") (pinfunction "2_2") (pintype "passive"))
      (node (ref "C51") (pin "1") (pinfunction "1_1") (pintype "passive"))
      (node (ref "C52") (pin "2") (pinfunction "C_2") (pintype "passive"))
      (node (ref "C55") (pin "C") (pinfunction "C_C") (pintype "passive"))
      (node (ref "C56") (pin "2") (pinfunction "2_2") (pintype "passive"))
      (node (ref "C57") (pin "2") (pinfunction "2_2") (pintype "passive"))
      (node (ref "C60") (pin "C") (pinfunction "C_C") (pintype "passive"))
      (node (ref "C62") (pin "C") (pinfunction "C_C") (pintype "passive"))
      (node (ref "D1") (pin "1") (pinfunction "GND_1") (pintype "passive"))
      (node (ref "J1") (pin "G") (pinfunction "G_G") (pintype "passive"))
      (node (ref "J2") (pin "A1") (pinfunction "A1_GND_A1") (pintype "passive"))
      (node (ref "J2") (pin "A12") (pinfunction "A12_GND_A12") (pintype "passive"))
      (node (ref "J2") (pin "B1") (pinfunction "B1_GND_B1") (pintype "passive"))
      (node (ref "J2") (pin "B12") (pinfunction "B12_GND_B12") (pintype "passive"))
      (node (ref "J2") (pin "GND@1") (pinfunction "CGND_GND@1") (pintype "passive"))
      (node (ref "J2") (pin "GND@2") (pinfunction "CGND_GND@2") (pintype "passive"))
      (node (ref "J2") (pin "GND@3") (pinfunction "CGND_GND@3") (pintype "passive"))
      (node (ref "J2") (pin "GND@4") (pinfunction "CGND_GND@4") (pintype "passive"))
      (node (ref "J3") (pin "5") (pinfunction "GND_5") (pintype "passive"))
      (node (ref "J3") (pin "SH1") (pinfunction "SHIELD_SH1") (pintype "passive"))
      (node (ref "J3") (pin "SH2") (pinfunction "SHIELD_SH2") (pintype "passive"))
      (node (ref "J3") (pin "SH3") (pinfunction "SHIELD_SH3") (pintype "passive"))
      (node (ref "J3") (pin "SH4") (pinfunction "SHIELD_SH4") (pintype "passive"))
      (node (ref "J3") (pin "SH5") (pinfunction "SHIELD_SH5") (pintype "passive"))
      (node (ref "J3") (pin "SH6") (pinfunction "SHIELD_SH6") (pintype "passive"))
      (node (ref "J3") (pin "SH7") (pinfunction "SHIELD_SH7") (pintype "passive"))
      (node (ref "J3") (pin "SH8") (pinfunction "SHIELD_SH8") (pintype "passive"))
      (node (ref "J5") (pin "1") (pinfunction "1_1") (pintype "passive"))
      (node (ref "J5") (pin "M1") (pinfunction "1_M1") (pintype "passive"))
      (node (ref "J5") (pin "M2") (pinfunction "2_M2") (pintype "passive"))
      (node (ref "J7") (pin "3") (pinfunction "3_3") (pintype "passive"))
      (node (ref "J7") (pin "M1") (pinfunction "1_M1") (pintype "passive"))
      (node (ref "J7") (pin "M2") (pinfunction "2_M2") (pintype "passive"))
      (node (ref "Q16") (pin "2") (pinfunction "S_2") (pintype "passive"))
      (node (ref "R15") (pin "2") (pinfunction "2_2") (pintype "passive"))
      (node (ref "R18") (pin "1") (pinfunction "1_1") (pintype "passive"))
      (node (ref "R2") (pin "2") (pinfunction "2_2") (pintype "passive"))
      (node (ref "R21") (pin "1") (pinfunction "1_1") (pintype "passive"))
      (node (ref "R3") (pin "2") (pinfunction "2_2") (pintype "passive"))
      (node (ref "R8") (pin "2") (pinfunction "2_2") (pintype "passive"))
      (node (ref "U1") (pin "2") (pinfunction "GND_2") (pintype "passive"))
      (node (ref "U10") (pin "4") (pinfunction "GND_4") (pintype "power_in"))
      (node (ref "U2") (pin "7") (pinfunction "GND_7") (pintype "passive"))
      (node (ref "U4") (pin "107") (pinfunction "VSS_107") (pintype "passive"))
      (node (ref "U4") (pin "120") (pinfunction "VSS_120") (pintype "passive"))
      (node (ref "U4") (pin "130") (pinfunction "VSS_130") (pintype "passive"))
      (node (ref "U4") (pin "16") (pinfunction "VSS_16") (pintype "passive"))
      (node (ref "U4") (pin "31") (pinfunction "VSSA_31") (pintype "passive"))
      (node (ref "U4") (pin "34") (pinfunction "PA0-WKUP/USART2_CTS/UART4_TX/ETH_MII_CRS/TIM2_CH1_ETR/TIM5_CH1/TIM8_ETR/EVENTOUT/ADC123_IN0_34") (pintype "passive"))
      (node (ref "U4") (pin "38") (pinfunction "VSS_38") (pintype "passive"))
      (node (ref "U4") (pin "51") (pinfunction "VSS_51") (pintype "passive"))
      (node (ref "U4") (pin "61") (pinfunction "VSS_61") (pintype "passive"))
      (node (ref "U4") (pin "83") (pinfunction "VSS_83") (pintype "passive"))
      (node (ref "U4") (pin "94") (pinfunction "VSS_94") (pintype "passive"))
      (node (ref "U5") (pin "8") (pinfunction "GND_8") (pintype "power_in"))
      (node (ref "U6") (pin "2") (pinfunction "GND_2") (pintype "power_in"))
      (node (ref "X2") (pin "GND@1") (pinfunction "1_GND@1") (pintype "passive"))
      (node (ref "X2") (pin "GND@2") (pinfunction "2_GND@2") (pintype "passive"))
    )
    (net (code "12") (name "I2S2_F_CK") (class "Default")
      (node (ref "R11") (pin "2") (pinfunction "2_2") (pintype "passive"))
      (node (ref "U4") (pin "74") (pinfunction "PB13/SPI2_SCK/I2S2_CK/USART3_CTS/TIM1_CH1N/CAN2_TX/OTG_HS_ULPI_D6/ETH_RMII_TXD1/ETH_MII_TXD1/EVENTOUT_74") (pintype "passive"))
    )
    (net (code "13") (name "I2S2_F_MCLK") (class "Default")
      (node (ref "R13") (pin "2") (pinfunction "2_2") (pintype "passive"))
      (node (ref "U4") (pin "96") (pinfunction "PC6/I2S2_MCK/TIM8_CH1/SDIO_D6/USART6_TX/DCMI_D0/TIM3_CH1/EVENTOUT_96") (pintype "passive"))
    )
    (net (code "14") (name "I2S2_F_WS") (class "Default")
      (node (ref "R12") (pin "2") (pinfunction "2_2") (pintype "passive"))
      (node (ref "U4") (pin "73") (pinfunction "PB12/SPI2_NSS/I2S2_WS/I2C2_SMBA/USART3_CK/TIM1_BKIN/CAN2_RX/OTG_HS_ULPI_D5/ETH_RMII_TXD0/ETH_MII_TXD0/OTG_HS_ID/EVENTOUT_73") (pintype "passive"))
    )
    (net (code "15") (name "I2SD_F_SDO") (class "Default")
      (node (ref "R10") (pin "2") (pinfunction "2_2") (pintype "passive"))
      (node (ref "U4") (pin "76") (pinfunction "PB15/SPI2_MOSI/I2S2_SD/TIM1_CH3N/TIM8_CH3N/TIM12_CH2/OTG_HS_DP/EVENTOUT_76") (pintype "passive"))
    )
    (net (code "16") (name "LCD_CS") (class "Default")
      (node (ref "U1") (pin "3") (pinfunction "CS_3") (pintype "passive"))
      (node (ref "U4") (pin "40") (pinfunction "PA4/SPI1_NSS/SPI3_NSS/USART2_CK/DCMI_HSYNC/OTG_HS_SOF/I2S3_WS/EVENTOUT/ADC12_IN4/DAC1_OUT_40") (pintype "passive"))
    )
    (net (code "17") (name "LCD_DC") (class "Default")
      (node (ref "U1") (pin "5") (pinfunction "DC_5") (pintype "passive"))
      (node (ref "U4") (pin "59") (pinfunction "PE8/FSMC_D5/TIM1/CH1N/EVENTOUT_59") (pintype "passive"))
    )
    (net (code "18") (name "LCD_LED") (class "Default")
      (node (ref "U1") (pin "8") (pinfunction "LED_8") (pintype "passive"))
      (node (ref "U4") (pin "60") (pinfunction "PE9/FSMC_D6/TIM1_CH1/EVENTOUT_60") (pintype "passive"))
    )
    (net (code "19") (name "LCD_RESET") (class "Default")
      (node (ref "U1") (pin "4") (pinfunction "RESET_4") (pintype "passive"))
      (node (ref "U4") (pin "58") (pinfunction "PE7/FSMC_D4/TIM1_ETR/EVENTOUT_58") (pintype "passive"))
    )
    (net (code "20") (name "MCU_USART1_RX") (class "Default")
      (node (ref "J5") (pin "4") (pinfunction "4_4") (pintype "passive"))
      (node (ref "U4") (pin "137") (pinfunction "PB7/I2C1_SDA/FSMC_NL/DCMI_VSYNC/USART1_RX/TIM4_CH2/EVENTOUT_137") (pintype "passive"))
    )
    (net (code "21") (name "MCU_USART1_TX") (class "Default")
      (node (ref "J5") (pin "3") (pinfunction "3_3") (pintype "passive"))
      (node (ref "U4") (pin "136") (pinfunction "PB6/I2C1_SCL/TIM4_CH1/CAN2_TX/DCMI_D5/USART1_TX/EVENTOUT_136") (pintype "passive"))
    )
    (net (code "22") (name "MCU_USART6_RX") (class "Default")
      (node (ref "J5") (pin "5") (pinfunction "5_5") (pintype "passive"))
      (node (ref "U4") (pin "124") (pinfunction "PG9/USART6_RX/FSMC_NE2/FSMC_NCE3/EVENTOUT_124") (pintype "passive"))
    )
    (net (code "23") (name "MCU_USART6_TX") (class "Default")
      (node (ref "J5") (pin "6") (pinfunction "6_6") (pintype "passive"))
      (node (ref "U4") (pin "129") (pinfunction "PG14/FSMC_A25/USART6_TX/ETH_MII_TXD1/ETH_RMII_TXD1/EVENTOUT_129") (pintype "passive"))
    )
    (net (code "24") (name "Net-(C49-A)") (class "Default")
      (node (ref "C49") (pin "1") (pinfunction "A_1") (pintype "passive"))
      (node (ref "C50") (pin "1") (pinfunction "1_1") (pintype "passive"))
      (node (ref "U5") (pin "5") (pinfunction "VQ_5") (pintype "passive"))
    )
    (net (code "25") (name "Net-(C52-A)") (class "Default")
      (node (ref "C52") (pin "1") (pinfunction "A_1") (pintype "passive"))
      (node (ref "L12") (pin "1") (pinfunction "1_1") (pintype "passive"))
      (node (ref "U5") (pin "9") (pinfunction "VA_9") (pintype "power_in"))
    )
    (net (code "26") (name "Net-(C53-Pad1)") (class "Default")
      (node (ref "C53") (pin "1") (pinfunction "1_1") (pintype "passive"))
      (node (ref "R1") (pin "2") (pinfunction "2_2") (pintype "passive"))
      (node (ref "R2") (pin "1") (pinfunction "1_1") (pintype "passive"))
    )
    (net (code "27") (name "Net-(C54-Pad1)") (class "Default")
      (node (ref "C54") (pin "1") (pinfunction "1_1") (pintype "passive"))
      (node (ref "R15") (pin "1") (pinfunction "1_1") (pintype "passive"))
      (node (ref "R17") (pin "2") (pinfunction "2_2") (pintype "passive"))
    )
    (net (code "28") (name "Net-(C56-Pad1)") (class "Default")
      (node (ref "C56") (pin "1") (pinfunction "1_1") (pintype "passive"))
      (node (ref "J1") (pin "L") (pinfunction "L_L") (pintype "passive"))
      (node (ref "J1") (pin "R") (pinfunction "R_R") (pintype "passive"))
      (node (ref "R1") (pin "1") (pinfunction "1_1") (pintype "passive"))
    )
    (net (code "29") (name "Net-(D2-PadA)") (class "Default")
      (node (ref "D2") (pin "A") (pinfunction "A_A") (pintype "passive"))
      (node (ref "R20") (pin "1") (pinfunction "1_1") (pintype "passive"))
      (node (ref "R22") (pin "1") (pinfunction "1_1") (pintype "passive"))
    )
    (net (code "30") (name "Net-(J2-A5_CC1)") (class "Default")
      (node (ref "J2") (pin "A5") (pinfunction "A5_CC1_A5") (pintype "passive"))
      (node (ref "R18") (pin "2") (pinfunction "2_2") (pintype "passive"))
    )
    (net (code "31") (name "Net-(J2-B5_CC2)") (class "Default")
      (node (ref "J2") (pin "B5") (pinfunction "B5_CC2_B5") (pintype "passive"))
      (node (ref "R21") (pin "2") (pinfunction "2_2") (pintype "passive"))
    )
    (net (code "32") (name "Net-(Q1-G)") (class "Default")
      (node (ref "Q1") (pin "1") (pinfunction "G_1") (pintype "passive"))
      (node (ref "Q16") (pin "3") (pinfunction "D_3") (pintype "passive"))
      (node (ref "R9") (pin "1") (pinfunction "1_1") (pintype "passive"))
    )
    (net (code "33") (name "Net-(Q16-G)") (class "Default")
      (node (ref "Q16") (pin "1") (pinfunction "G_1") (pintype "passive"))
      (node (ref "R14") (pin "2") (pinfunction "2_2") (pintype "passive"))
      (node (ref "U4") (pin "119") (pinfunction "PD5/FSMC_NWE/USART2_TX/EVENTOUT_119") (pintype "passive"))
    )
    (net (code "34") (name "Net-(U2-BYPASS)") (class "Default")
      (node (ref "C1") (pin "1") (pinfunction "1_1") (pintype "passive"))
      (node (ref "U2") (pin "2") (pinfunction "BYPASS_2") (pintype "passive"))
      (node (ref "U2") (pin "3") (pinfunction "IN+_3") (pintype "passive"))
    )
    (net (code "35") (name "Net-(U2-IN-)") (class "Default")
      (node (ref "C3") (pin "1") (pinfunction "1_1") (pintype "passive"))
      (node (ref "C57") (pin "1") (pinfunction "1_1") (pintype "passive"))
      (node (ref "R17") (pin "1") (pinfunction "1_1") (pintype "passive"))
      (node (ref "R4") (pin "1") (pinfunction "1_1") (pintype "passive"))
      (node (ref "U2") (pin "4") (pinfunction "IN-_4") (pintype "passive"))
    )
    (net (code "36") (name "Net-(U2-OUT+)") (class "Default")
      (node (ref "J4") (pin "R") (pinfunction "R_R") (pintype "passive"))
      (node (ref "U2") (pin "8") (pinfunction "OUT+_8") (pintype "passive"))
    )
    (net (code "37") (name "Net-(U2-OUT-)") (class "Default")
      (node (ref "C3") (pin "2") (pinfunction "2_2") (pintype "passive"))
      (node (ref "J4") (pin "G") (pinfunction "G_G") (pintype "passive"))
      (node (ref "R4") (pin "2") (pinfunction "2_2") (pintype "passive"))
      (node (ref "U2") (pin "5") (pinfunction "OUT-_5") (pintype "passive"))
    )
    (net (code "38") (name "Net-(U4A-PA11{slash}USART1_CTS{slash}CAN1_RX{slash}TIM1_CH4{slash}OTG_FS_DM{slash}EVENTOUT)") (class "Default")
      (node (ref "R34") (pin "1") (pinfunction "1_1") (pintype "passive"))
      (node (ref "U4") (pin "103") (pinfunction "PA11/USART1_CTS/CAN1_RX/TIM1_CH4/OTG_FS_DM/EVENTOUT_103") (pintype "passive"))
    )
    (net (code "39") (name "Net-(U4A-PA12{slash}USART1_RTS{slash}CAN1_TX{slash}TIM1_ETR{slash}OTG_FS_DP{slash}EVENTOUT)") (class "Default")
      (node (ref "R19") (pin "2") (pinfunction "2_2") (pintype "passive"))
      (node (ref "R35") (pin "1") (pinfunction "1_1") (pintype "passive"))
      (node (ref "U4") (pin "104") (pinfunction "PA12/USART1_RTS/CAN1_TX/TIM1_ETR/OTG_FS_DP/EVENTOUT_104") (pintype "passive"))
    )
    (net (code "40") (name "Net-(U4C-PH0-OSC_IN{slash}EVENTOUT)") (class "Default")
      (node (ref "C45") (pin "2") (pinfunction "2_2") (pintype "passive"))
      (node (ref "U4") (pin "23") (pinfunction "PH0-OSC_IN/EVENTOUT_23") (pintype "passive"))
      (node (ref "X2") (pin "1") (pinfunction "P$1_1") (pintype "passive"))
    )
    (net (code "41") (name "Net-(U4C-PH1-OSC_OUT{slash}EVENTOUT)") (class "Default")
      (node (ref "C47") (pin "2") (pinfunction "2_2") (pintype "passive"))
      (node (ref "U4") (pin "24") (pinfunction "PH1-OSC_OUT/EVENTOUT_24") (pintype "passive"))
      (node (ref "X2") (pin "3") (pinfunction "P$2_3") (pintype "passive"))
    )
    (net (code "42") (name "Net-(U4C-VCAP_1)") (class "Default")
      (node (ref "C46") (pin "A") (pinfunction "A_A") (pintype "passive"))
      (node (ref "U4") (pin "71") (pinfunction "VCAP_1_71") (pintype "passive"))
    )
    (net (code "43") (name "Net-(U4C-VCAP_2)") (class "Default")
      (node (ref "C48") (pin "A") (pinfunction "A_A") (pintype "passive"))
      (node (ref "U4") (pin "106") (pinfunction "VCAP_2_106") (pintype "passive"))
    )
    (net (code "44") (name "Net-(U5--DEM{slash}SCLK)") (class "Default")
      (node (ref "R11") (pin "1") (pinfunction "1_1") (pintype "passive"))
      (node (ref "U5") (pin "2") (pinfunction "-DEM/SCLK_2") (pintype "input"))
    )
    (net (code "45") (name "Net-(U5-AOUTL)") (class "Default")
      (node (ref "C53") (pin "2") (pinfunction "2_2") (pintype "passive"))
      (node (ref "U5") (pin "7") (pinfunction "AOUTL_7") (pintype "output"))
    )
    (net (code "46") (name "Net-(U5-AOUTR)") (class "Default")
      (node (ref "C54") (pin "2") (pinfunction "2_2") (pintype "passive"))
      (node (ref "U5") (pin "10") (pinfunction "AOUTR_10") (pintype "output"))
    )
    (net (code "47") (name "Net-(U5-FILT+)") (class "Default")
      (node (ref "C51") (pin "2") (pinfunction "2_2") (pintype "passive"))
      (node (ref "U5") (pin "6") (pinfunction "FILT+_6") (pintype "passive"))
    )
    (net (code "48") (name "Net-(U5-LRCLK)") (class "Default")
      (node (ref "R12") (pin "1") (pinfunction "1_1") (pintype "passive"))
      (node (ref "U5") (pin "3") (pinfunction "LRCLK_3") (pintype "input"))
    )
    (net (code "49") (name "Net-(U5-MCLK)") (class "Default")
      (node (ref "R13") (pin "1") (pinfunction "1_1") (pintype "passive"))
      (node (ref "U5") (pin "4") (pinfunction "MCLK_4") (pintype "input"))
    )
    (net (code "50") (name "Net-(U5-SDIN)") (class "Default")
      (node (ref "R10") (pin "1") (pinfunction "1_1") (pintype "passive"))
      (node (ref "U5") (pin "1") (pinfunction "SDIN_1") (pintype "input"))
    )
    (net (code "51") (name "SD_CS") (class "Default")
      (node (ref "U1") (pin "18") (pinfunction "SD_CS_18") (pintype "passive"))
      (node (ref "U4") (pin "126") (pinfunction "PG11/FSMC_NCE4_2/ETH_MII_TX_EN/ETH_RMII_TX_EN/EVENTOUT_126") (pintype "passive"))
    )
    (net (code "52") (name "SPI1_MISO") (class "Default")
      (node (ref "R5") (pin "1") (pinfunction "1_1") (pintype "passive"))
      (node (ref "U1") (pin "9") (pinfunction "SDO/MISO_9") (pintype "passive"))
      (node (ref "U10") (pin "2") (pinfunction "SO_2") (pintype "output"))
      (node (ref "U4") (pin "42") (pinfunction "PA6/SPI1_MISO/TIM8_BKIN/TIM13_CH1/DCMI_PIXCLK/TIM3_CH1/TIM1_BKIN/EVENTOUT/ADC12_IN6_42") (pintype "passive"))
    )
    (net (code "53") (name "SPI1_MOSI") (class "Default")
      (node (ref "U1") (pin "6") (pinfunction "SDI/MOSI_6") (pintype "passive"))
      (node (ref "U10") (pin "5") (pinfunction "SI_5") (pintype "input"))
      (node (ref "U4") (pin "43") (pinfunction "PA7/SPI1_MOSI/TIM8_CH1N/TIM14_CH1/TIM3_CH2/ETH_MII_RX_DV/TIM1_CH1N/RMII_CRS_DV/EVENTOUT/ADC12_IN7_43") (pintype "passive"))
    )
    (net (code "54") (name "SPI1_SCK") (class "Default")
      (node (ref "U1") (pin "7") (pinfunction "SCK_7") (pintype "passive"))
      (node (ref "U10") (pin "6") (pinfunction "SCK_6") (pintype "input"))
      (node (ref "U4") (pin "41") (pinfunction "PA5/SPI1_SCK/OTG_HS_ULPI_CK/TIM2_CH1_ETR/TIM8_CHIN/EVENTOUT/ADC12_IN5/DAC2_OUT_41") (pintype "passive"))
    )
    (net (code "55") (name "SPI3_MISO") (class "Default")
      (node (ref "R16") (pin "2") (pinfunction "2_2") (pintype "passive"))
      (node (ref "U1") (pin "16") (pinfunction "SD_MISO_16") (pintype "passive"))
      (node (ref "U4") (pin "112") (pinfunction "PC11/UART4_RX/SPI3_MISO/SDIO_D3/DCMI_D4/USART3_RX/I2S3EXT_SD/EVENTOUT_112") (pintype "passive"))
    )
    (net (code "56") (name "SPI3_MOSI") (class "Default")
      (node (ref "U1") (pin "17") (pinfunction "SD_MOSI_17") (pintype "passive"))
      (node (ref "U4") (pin "113") (pinfunction "PC12/UART5_TX/SDIO_CK/DCMI_D9/SPI3_MOSI/I2S3_SD/USART3_CK/EVENTOUT_113") (pintype "passive"))
    )
    (net (code "57") (name "SPI3_SCLK") (class "Default")
      (node (ref "U1") (pin "15") (pinfunction "SD_SCK_15") (pintype "passive"))
      (node (ref "U4") (pin "111") (pinfunction "PC10/SPI3_SCK/I2S3_CK/UART4_TX/SDIO_D2/DCMI_D8/USART3_TX/EVENTOUT_111") (pintype "passive"))
    )
    (net (code "58") (name "SWCLK") (class "Default")
      (node (ref "J7") (pin "2") (pinfunction "2_2") (pintype "passive"))
      (node (ref "U4") (pin "109") (pinfunction "PA14/JTCK-SWCLK/EVENTOUT_109") (pintype "passive"))
    )
    (net (code "59") (name "SWDIO") (class "Default")
      (node (ref "J7") (pin "4") (pinfunction "4_4") (pintype "passive"))
      (node (ref "U4") (pin "105") (pinfunction "PA13/JTMS-SWDIO/EVENTOUT_105") (pintype "passive"))
    )
    (net (code "60") (name "SWO{slash}I2S3_F_CK") (class "Default")
      (node (ref "J7") (pin "6") (pinfunction "6_6") (pintype "passive"))
      (node (ref "U4") (pin "133") (pinfunction "PB3/JTDO/TRACESWO/SPI3_SCK/I2S3_CK/TIM2_CH2/SPI1_SCK/EVENTOUT_133") (pintype "passive"))
    )
    (net (code "61") (name "TOUCH_CS") (class "Default")
      (node (ref "U1") (pin "11") (pinfunction "T_CS_11") (pintype "passive"))
      (node (ref "U4") (pin "37") (pinfunction "PA3/USART2_RX/TIM5_CH4/TIM9_CH2/TIM2_CH4/OTG_HS_ULPI_D0/ETH_MII_COL/EVENTOUT/ADC123_IN3_37") (pintype "passive"))
    )
    (net (code "62") (name "TOUCH_DIN") (class "Default")
      (node (ref "U1") (pin "12") (pinfunction "T_DIN_12") (pintype "passive"))
      (node (ref "U4") (pin "65") (pinfunction "PE12/FSMC_D9/TIM1_CH3N/EVENTOUT_65") (pintype "passive"))
    )
    (net (code "63") (name "TOUCH_DOUT") (class "Default")
      (node (ref "U1") (pin "13") (pinfunction "T_DO_13") (pintype "passive"))
      (node (ref "U4") (pin "64") (pinfunction "PE11/FSMC_D8/TIM1_CH2/EVENTOUT_64") (pintype "passive"))
    )
    (net (code "64") (name "TOUCH_IRQ") (class "Default")
      (node (ref "U1") (pin "14") (pinfunction "T_IRQ_14") (pintype "passive"))
      (node (ref "U4") (pin "66") (pinfunction "PE13/FSMC_D10/TIM1_CH3/EVENTOUT_66") (pintype "passive"))
    )
    (net (code "65") (name "TOUCH_SCK") (class "Default")
      (node (ref "U1") (pin "10") (pinfunction "T_CLK_10") (pintype "passive"))
      (node (ref "U4") (pin "63") (pinfunction "PE10/FSMC_D7/TIM1_CH2N/EVENTOUT_63") (pintype "passive"))
    )
    (net (code "66") (name "USB_N") (class "Default")
      (node (ref "D1") (pin "2") (pinfunction "I/O_2") (pintype "passive"))
      (node (ref "J3") (pin "2") (pinfunction "D-_2") (pintype "passive"))
      (node (ref "R34") (pin "2") (pinfunction "2_2") (pintype "passive"))
    )
    (net (code "67") (name "USB_OTG_FS_ID") (class "Default")
      (node (ref "J3") (pin "4") (pinfunction "ID_4") (pintype "passive"))
      (node (ref "R6") (pin "1") (pinfunction "1_1") (pintype "passive"))
      (node (ref "U4") (pin "102") (pinfunction "PA10/USART1_RX/TIM1_CH/OTG_FS_ID/DCMI_D1/EVENTOUT_102") (pintype "passive"))
    )
    (net (code "68") (name "USB_P") (class "Default")
      (node (ref "D1") (pin "3") (pinfunction "I/O_3") (pintype "passive"))
      (node (ref "J3") (pin "3") (pinfunction "D+_3") (pintype "passive"))
      (node (ref "R35") (pin "2") (pinfunction "2_2") (pintype "passive"))
    )
    (net (code "69") (name "USB_TYPEC_DET") (class "Default")
      (node (ref "R22") (pin "2") (pinfunction "2_2") (pintype "passive"))
      (node (ref "U4") (pin "110") (pinfunction "PA15/JTDI/SPI3_NSS/I2S3_WS/TIM2_CH1_ETR/SPI1_NSS/EVENTOUT_110") (pintype "passive"))
    )
    (net (code "70") (name "VBUS") (class "Default")
      (node (ref "J2") (pin "A4") (pinfunction "A4_VBUS_A4") (pintype "passive"))
      (node (ref "J2") (pin "A9") (pinfunction "A9_VBUS_A9") (pintype "passive"))
      (node (ref "J2") (pin "B4") (pinfunction "B4_VBUS_B4") (pintype "passive"))
      (node (ref "J2") (pin "B9") (pinfunction "B9_VBUS_B9") (pintype "passive"))
      (node (ref "R20") (pin "2") (pinfunction "2_2") (pintype "passive"))
    )
    (net (code "71") (name "VBUS_5V") (class "Default")
      (node (ref "J3") (pin "1") (pinfunction "VBUS_1") (pintype "passive"))
      (node (ref "Q1") (pin "4") (pinfunction "D_4") (pintype "passive"))
      (node (ref "U4") (pin "101") (pinfunction "PA9/USART1_TX/TIM1_CH2/I2C3_SMBA/DCMI_D0/EVENTOUT_101") (pintype "passive"))
    )
    (net (code "72") (name "unconnected-(J2-A6_DP1-PadA6)") (class "Default")
      (node (ref "J2") (pin "A6") (pinfunction "A6_DP1_A6") (pintype "passive"))
    )
    (net (code "73") (name "unconnected-(J2-A7_DN1-PadA7)") (class "Default")
      (node (ref "J2") (pin "A7") (pinfunction "A7_DN1_A7") (pintype "passive"))
    )
    (net (code "74") (name "unconnected-(J2-A8_SBU1-PadA8)") (class "Default")
      (node (ref "J2") (pin "A8") (pinfunction "A8_SBU1_A8") (pintype "passive"))
    )
    (net (code "75") (name "unconnected-(J2-B6_DP2-PadB6)") (class "Default")
      (node (ref "J2") (pin "B6") (pinfunction "B6_DP2_B6") (pintype "passive"))
    )
    (net (code "76") (name "unconnected-(J2-B7_DN2-PadB7)") (class "Default")
      (node (ref "J2") (pin "B7") (pinfunction "B7_DN2_B7") (pintype "passive"))
    )
    (net (code "77") (name "unconnected-(J2-B8_SBU2-PadB8)") (class "Default")
      (node (ref "J2") (pin "B8") (pinfunction "B8_SBU2_B8") (pintype "passive"))
    )
    (net (code "78") (name "unconnected-(J4-PadL)") (class "Default")
      (node (ref "J4") (pin "L") (pinfunction "L_L") (pintype "passive"))
    )
    (net (code "79") (name "unconnected-(J5-Pad2)") (class "Default")
      (node (ref "J5") (pin "2") (pinfunction "2_2") (pintype "passive"))
    )
    (net (code "80") (name "unconnected-(J7-Pad1)") (class "Default")
      (node (ref "J7") (pin "1") (pinfunction "1_1") (pintype "passive"))
    )
    (net (code "81") (name "unconnected-(U4A-PA2{slash}USART2_TX{slash}TIM5_CH3{slash}TIM9_CH1{slash}TIM2_CH3{slash}ETH_MDIO{slash}EVENTOUT{slash}ADC123_IN2-Pad36)") (class "Default")
      (node (ref "U4") (pin "36") (pinfunction "PA2/USART2_TX/TIM5_CH3/TIM9_CH1/TIM2_CH3/ETH_MDIO/EVENTOUT/ADC123_IN2_36") (pintype "passive"))
    )
    (net (code "82") (name "unconnected-(U4A-PA8{slash}MC01{slash}USART1_CK{slash}TIM1_CH1{slash}I2C3_SCL{slash}OTG_FS_SOF{slash}EVENTOUT-Pad100)") (class "Default")
      (node (ref "U4") (pin "100") (pinfunction "PA8/MC01/USART1_CK/TIM1_CH1/I2C3_SCL/OTG_FS_SOF/EVENTOUT_100") (pintype "passive"))
    )
    (net (code "83") (name "unconnected-(U4A-PB0{slash}TIM3_CH3{slash}TIM8_CH2N{slash}OTG_HS_ULPI_D1{slash}ETH_MII_RXD2{slash}TIM1_CH2N{slash}EVENTOUT{slash}ADC12_IN8-Pad46)") (class "Default")
      (node (ref "U4") (pin "46") (pinfunction "PB0/TIM3_CH3/TIM8_CH2N/OTG_HS_ULPI_D1/ETH_MII_RXD2/TIM1_CH2N/EVENTOUT/ADC12_IN8_46") (pintype "passive"))
    )
    (net (code "84") (name "unconnected-(U4A-PB1{slash}TIM3_CH4{slash}TIM8_CH3N{slash}OTG_HS_ULPI_D2{slash}ETH_MII_RXD3{slash}TIM1_CH3N{slash}EVENTOUT{slash}ADC12_IN9-Pad47)") (class "Default")
      (node (ref "U4") (pin "47") (pinfunction "PB1/TIM3_CH4/TIM8_CH3N/OTG_HS_ULPI_D2/ETH_MII_RXD3/TIM1_CH3N/EVENTOUT/ADC12_IN9_47") (pintype "passive"))
    )
    (net (code "85") (name "unconnected-(U4A-PB2-BOOT1{slash}EVENTOUT-Pad48)") (class "Default")
      (node (ref "U4") (pin "48") (pinfunction "PB2-BOOT1/EVENTOUT_48") (pintype "passive"))
    )
    (net (code "86") (name "unconnected-(U4A-PB4{slash}NJTRST{slash}SPI3_MISO{slash}TIM3_CH1{slash}SPI1_MISO{slash}I2S3EXT_SD{slash}EVENTOUT-Pad134)") (class "Default")
      (node (ref "U4") (pin "134") (pinfunction "PB4/NJTRST/SPI3_MISO/TIM3_CH1/SPI1_MISO/I2S3EXT_SD/EVENTOUT_134") (pintype "passive"))
    )
    (net (code "87") (name "unconnected-(U4A-PB5{slash}I2C1_SMBA{slash}CAN2_RX{slash}OTG_HS_ULPI_D7{slash}ETH_PPS_OUT{slash}TIM3_CH2{slash}SPI1_MOSI{slash}SPI3_MOSI{slash}DCMI_D10{slash}I2S3_SD{slash}EVENTOUT-Pad135)") (class "Default")
      (node (ref "U4") (pin "135") (pinfunction "PB5/I2C1_SMBA/CAN2_RX/OTG_HS_ULPI_D7/ETH_PPS_OUT/TIM3_CH2/SPI1_MOSI/SPI3_MOSI/DCMI_D10/I2S3_SD/EVENTOUT_135") (pintype "passive"))
    )
    (net (code "88") (name "unconnected-(U4A-PB8{slash}TIM4_CH3{slash}SDIO_D4{slash}TIM10_CH1{slash}DCMI_D6{slash}ETH_MII_TXD3{slash}I2C1_SCL{slash}CAN1_RX{slash}EVENTOUT-Pad139)") (class "Default")
      (node (ref "U4") (pin "139") (pinfunction "PB8/TIM4_CH3/SDIO_D4/TIM10_CH1/DCMI_D6/ETH_MII_TXD3/I2C1_SCL/CAN1_RX/EVENTOUT_139") (pintype "passive"))
    )
    (net (code "89") (name "unconnected-(U4A-PB9{slash}SPI2_NSS{slash}I2S2_WS{slash}TIM4_CH4{slash}TIM11_CH1{slash}SDIO_D5{slash}DCMI_D7{slash}I2C1_SDA{slash}CAN1_TX{slash}EVENTOUT-Pad140)") (class "Default")
      (node (ref "U4") (pin "140") (pinfunction "PB9/SPI2_NSS/I2S2_WS/TIM4_CH4/TIM11_CH1/SDIO_D5/DCMI_D7/I2C1_SDA/CAN1_TX/EVENTOUT_140") (pintype "passive"))
    )
    (net (code "90") (name "unconnected-(U4A-PB10{slash}SPI2_SCK{slash}I2S2_CK{slash}I2C2_SCL{slash}USART3_TX{slash}OTG_HS_ULPI_D3{slash}ETH_MII_RX_ER{slash}TIM2_CH3{slash}EVENTOUT-Pad69)") (class "Default")
      (node (ref "U4") (pin "69") (pinfunction "PB10/SPI2_SCK/I2S2_CK/I2C2_SCL/USART3_TX/OTG_HS_ULPI_D3/ETH_MII_RX_ER/TIM2_CH3/EVENTOUT_69") (pintype "passive"))
    )
    (net (code "91") (name "unconnected-(U4A-PB11{slash}I2C2_SDA{slash}USART3_RX{slash}OTG_HS_ULPI_D4{slash}ETH_RMII_TX_EN{slash}ETH_MII_TX_EN{slash}TIM2_CH4{slash}EVENTOUT-Pad70)") (class "Default")
      (node (ref "U4") (pin "70") (pinfunction "PB11/I2C2_SDA/USART3_RX/OTG_HS_ULPI_D4/ETH_RMII_TX_EN/ETH_MII_TX_EN/TIM2_CH4/EVENTOUT_70") (pintype "passive"))
    )
    (net (code "92") (name "unconnected-(U4A-PB14{slash}SPI2_MISO{slash}TIM1_CH2N{slash}TIM12_CH1{slash}OTG_HS_DM{slash}USART3_RTS{slash}TIM8_CH2N{slash}I2S2EXT_SD{slash}EVENTOUT-Pad75)") (class "Default")
      (node (ref "U4") (pin "75") (pinfunction "PB14/SPI2_MISO/TIM1_CH2N/TIM12_CH1/OTG_HS_DM/USART3_RTS/TIM8_CH2N/I2S2EXT_SD/EVENTOUT_75") (pintype "passive"))
    )
    (net (code "93") (name "unconnected-(U4A-PC0{slash}OTG_HS_ULPI_STP{slash}EVENTOUT{slash}ADC123_IN10-Pad26)") (class "Default")
      (node (ref "U4") (pin "26") (pinfunction "PC0/OTG_HS_ULPI_STP/EVENTOUT/ADC123_IN10_26") (pintype "passive"))
    )
    (net (code "94") (name "unconnected-(U4A-PC1{slash}ETH_MDC{slash}EVENTOUT{slash}ADC123_IN11-Pad27)") (class "Default")
      (node (ref "U4") (pin "27") (pinfunction "PC1/ETH_MDC/EVENTOUT/ADC123_IN11_27") (pintype "passive"))
    )
    (net (code "95") (name "unconnected-(U4A-PC3{slash}SPI2_MOSI{slash}I2S2_SD{slash}OTG_HS_ULPI_NXT{slash}ETH_MII_TX_CLK{slash}EVENTOUT{slash}ADC123_IN13-Pad29)") (class "Default")
      (node (ref "U4") (pin "29") (pinfunction "PC3/SPI2_MOSI/I2S2_SD/OTG_HS_ULPI_NXT/ETH_MII_TX_CLK/EVENTOUT/ADC123_IN13_29") (pintype "passive"))
    )
    (net (code "96") (name "unconnected-(U4A-PC4{slash}ETH_RMII_RX_D0{slash}ETH_MII_RX_D0{slash}ADC12_IN14-Pad44)") (class "Default")
      (node (ref "U4") (pin "44") (pinfunction "PC4/ETH_RMII_RX_D0/ETH_MII_RX_D0/ADC12_IN14_44") (pintype "passive"))
    )
    (net (code "97") (name "unconnected-(U4A-PC5{slash}ETH_RMII_RX_D1{slash}ETH_MII_RX_D1{slash}EVENTOUT{slash}ADC12_IN15-Pad45)") (class "Default")
      (node (ref "U4") (pin "45") (pinfunction "PC5/ETH_RMII_RX_D1/ETH_MII_RX_D1/EVENTOUT/ADC12_IN15_45") (pintype "passive"))
    )
    (net (code "98") (name "unconnected-(U4A-PC7{slash}I2S3_MCK{slash}TIM8_CH2{slash}SDIO_D7{slash}USART6_RX{slash}DCMI_D1{slash}TIM3_CH2{slash}EVENTOUT-Pad97)") (class "Default")
      (node (ref "U4") (pin "97") (pinfunction "PC7/I2S3_MCK/TIM8_CH2/SDIO_D7/USART6_RX/DCMI_D1/TIM3_CH2/EVENTOUT_97") (pintype "passive"))
    )
    (net (code "99") (name "unconnected-(U4A-PC9{slash}I2S_CKIN{slash}MC02{slash}TIM8_CH4{slash}SDIO_D1{slash}I2C3_SDA{slash}DCMI_D3{slash}TIM3_CH4{slash}EVENTOUT-Pad99)") (class "Default")
      (node (ref "U4") (pin "99") (pinfunction "PC9/I2S_CKIN/MC02/TIM8_CH4/SDIO_D1/I2C3_SDA/DCMI_D3/TIM3_CH4/EVENTOUT_99") (pintype "passive"))
    )
    (net (code "100") (name "unconnected-(U4A-PC13_DNU_{slash}EVENTOUT{slash}RTC_AF2{slash}-Pad7)") (class "Default")
      (node (ref "U4") (pin "7") (pinfunction "PC13_DNU_/EVENTOUT/RTC_AF2/_7") (pintype "passive"))
    )
    (net (code "101") (name "unconnected-(U4A-PC14-OSC32_IN_DNU_{slash}EVENTOUT-Pad8)") (class "Default")
      (node (ref "U4") (pin "8") (pinfunction "PC14-OSC32_IN_DNU_/EVENTOUT_8") (pintype "passive"))
    )
    (net (code "102") (name "unconnected-(U4A-PC15-OSC32_OUT_DNU_{slash}EVENTOUT-Pad9)") (class "Default")
      (node (ref "U4") (pin "9") (pinfunction "PC15-OSC32_OUT_DNU_/EVENTOUT_9") (pintype "passive"))
    )
    (net (code "103") (name "unconnected-(U4B-PD0{slash}FSMC_D2{slash}CAN1_RX{slash}EVENTOUT-Pad114)") (class "Default")
      (node (ref "U4") (pin "114") (pinfunction "PD0/FSMC_D2/CAN1_RX/EVENTOUT_114") (pintype "passive"))
    )
    (net (code "104") (name "unconnected-(U4B-PD1{slash}FSMC_D3{slash}CAN1_TX{slash}EVENTOUT-Pad115)") (class "Default")
      (node (ref "U4") (pin "115") (pinfunction "PD1/FSMC_D3/CAN1_TX/EVENTOUT_115") (pintype "passive"))
    )
    (net (code "105") (name "unconnected-(U4B-PD2{slash}TIM3_ETR{slash}UART5_RX{slash}SDIO_CMD{slash}DCMI_D11{slash}EVENTOUT-Pad116)") (class "Default")
      (node (ref "U4") (pin "116") (pinfunction "PD2/TIM3_ETR/UART5_RX/SDIO_CMD/DCMI_D11/EVENTOUT_116") (pintype "passive"))
    )
    (net (code "106") (name "unconnected-(U4B-PD3{slash}FSMC_CLK{slash}USART2_CTS{slash}EVENTOUT-Pad117)") (class "Default")
      (node (ref "U4") (pin "117") (pinfunction "PD3/FSMC_CLK/USART2_CTS/EVENTOUT_117") (pintype "passive"))
    )
    (net (code "107") (name "unconnected-(U4B-PD4{slash}FSMC_NOE{slash}USART2_RTS{slash}EVENTOUT-Pad118)") (class "Default")
      (node (ref "U4") (pin "118") (pinfunction "PD4/FSMC_NOE/USART2_RTS/EVENTOUT_118") (pintype "passive"))
    )
    (net (code "108") (name "unconnected-(U4B-PD6{slash}FSMC_NWAIT{slash}USART2_RX{slash}EVENTOUT-Pad122)") (class "Default")
      (node (ref "U4") (pin "122") (pinfunction "PD6/FSMC_NWAIT/USART2_RX/EVENTOUT_122") (pintype "passive"))
    )
    (net (code "109") (name "unconnected-(U4B-PD7{slash}USART2_CK{slash}FSMC_NE1{slash}FSMC_NCE2{slash}EVENTOUT-Pad123)") (class "Default")
      (node (ref "U4") (pin "123") (pinfunction "PD7/USART2_CK/FSMC_NE1/FSMC_NCE2/EVENTOUT_123") (pintype "passive"))
    )
    (net (code "110") (name "unconnected-(U4B-PD8{slash}FSMC_D13{slash}USART3_TX{slash}EVENTOUT-Pad77)") (class "Default")
      (node (ref "U4") (pin "77") (pinfunction "PD8/FSMC_D13/USART3_TX/EVENTOUT_77") (pintype "passive"))
    )
    (net (code "111") (name "unconnected-(U4B-PD9{slash}FSMC_D14{slash}USART3_RX{slash}EVENTOUT-Pad78)") (class "Default")
      (node (ref "U4") (pin "78") (pinfunction "PD9/FSMC_D14/USART3_RX/EVENTOUT_78") (pintype "passive"))
    )
    (net (code "112") (name "unconnected-(U4B-PD10{slash}FSMC_D15{slash}USART3_CK{slash}EVENTOUT-Pad79)") (class "Default")
      (node (ref "U4") (pin "79") (pinfunction "PD10/FSMC_D15/USART3_CK/EVENTOUT_79") (pintype "passive"))
    )
    (net (code "113") (name "unconnected-(U4B-PD11{slash}FSMC_CLE{slash}FSMC_A16{slash}USART3_CTS{slash}EVENTOUT-Pad80)") (class "Default")
      (node (ref "U4") (pin "80") (pinfunction "PD11/FSMC_CLE/FSMC_A16/USART3_CTS/EVENTOUT_80") (pintype "passive"))
    )
    (net (code "114") (name "unconnected-(U4B-PD12{slash}FSMC_ALE{slash}FSMC_A17{slash}TIM4_CH1{slash}USART3_RTS{slash}EVENTOUT-Pad81)") (class "Default")
      (node (ref "U4") (pin "81") (pinfunction "PD12/FSMC_ALE/FSMC_A17/TIM4_CH1/USART3_RTS/EVENTOUT_81") (pintype "passive"))
    )
    (net (code "115") (name "unconnected-(U4B-PD13{slash}FSMC_A18{slash}TIM4_CH2{slash}EVENTOUT-Pad82)") (class "Default")
      (node (ref "U4") (pin "82") (pinfunction "PD13/FSMC_A18/TIM4_CH2/EVENTOUT_82") (pintype "passive"))
    )
    (net (code "116") (name "unconnected-(U4B-PD14{slash}FSMC_D0{slash}TIM4_CH3{slash}EVENTOUT-Pad85)") (class "Default")
      (node (ref "U4") (pin "85") (pinfunction "PD14/FSMC_D0/TIM4_CH3/EVENTOUT_85") (pintype "passive"))
    )
    (net (code "117") (name "unconnected-(U4B-PD15{slash}FSMC_D1{slash}TIM4_CH4{slash}EVENTOUT-Pad86)") (class "Default")
      (node (ref "U4") (pin "86") (pinfunction "PD15/FSMC_D1/TIM4_CH4/EVENTOUT_86") (pintype "passive"))
    )
    (net (code "118") (name "unconnected-(U4B-PE0{slash}TIM4_ETR{slash}FSMC_NBLO{slash}DCMI_D2{slash}EVENTOUT-Pad141)") (class "Default")
      (node (ref "U4") (pin "141") (pinfunction "PE0/TIM4_ETR/FSMC_NBLO/DCMI_D2/EVENTOUT_141") (pintype "passive"))
    )
    (net (code "119") (name "unconnected-(U4B-PE1{slash}FSMC_NBL1{slash}DMI_D3{slash}EVENTOUT-Pad142)") (class "Default")
      (node (ref "U4") (pin "142") (pinfunction "PE1/FSMC_NBL1/DMI_D3/EVENTOUT_142") (pintype "passive"))
    )
    (net (code "120") (name "unconnected-(U4B-PE2{slash}TRACECLK{slash}FSMC_A23{slash}ETH_MII_TXD3{slash}EVENTOUT-Pad1)") (class "Default")
      (node (ref "U4") (pin "1") (pinfunction "PE2/TRACECLK/FSMC_A23/ETH_MII_TXD3/EVENTOUT_1") (pintype "passive"))
    )
    (net (code "121") (name "unconnected-(U4B-PE3{slash}TRACED0{slash}FSMC_A19{slash}EVENTOUT-Pad2)") (class "Default")
      (node (ref "U4") (pin "2") (pinfunction "PE3/TRACED0/FSMC_A19/EVENTOUT_2") (pintype "passive"))
    )
    (net (code "122") (name "unconnected-(U4B-PE4{slash}TRACED1{slash}FSMC_A20{slash}DCMI_D4{slash}EVENTOUT-Pad3)") (class "Default")
      (node (ref "U4") (pin "3") (pinfunction "PE4/TRACED1/FSMC_A20/DCMI_D4/EVENTOUT_3") (pintype "passive"))
    )
    (net (code "123") (name "unconnected-(U4B-PE5{slash}TRACED2{slash}FSMC_A21{slash}TIM9_CH1{slash}DCMI_D6{slash}EVENTOUT-Pad4)") (class "Default")
      (node (ref "U4") (pin "4") (pinfunction "PE5/TRACED2/FSMC_A21/TIM9_CH1/DCMI_D6/EVENTOUT_4") (pintype "passive"))
    )
    (net (code "124") (name "unconnected-(U4B-PE6{slash}TRACED3{slash}FSMC_A22{slash}TIM9_CH2{slash}DCMI_D7{slash}EVENTOUT-Pad5)") (class "Default")
      (node (ref "U4") (pin "5") (pinfunction "PE6/TRACED3/FSMC_A22/TIM9_CH2/DCMI_D7/EVENTOUT_5") (pintype "passive"))
    )
    (net (code "125") (name "unconnected-(U4B-PE14{slash}FSMC_D11{slash}TIM1_CH4{slash}EVENTOUT-Pad67)") (class "Default")
      (node (ref "U4") (pin "67") (pinfunction "PE14/FSMC_D11/TIM1_CH4/EVENTOUT_67") (pintype "passive"))
    )
    (net (code "126") (name "unconnected-(U4B-PE15{slash}FSMC_D12{slash}TIM1_BKIN{slash}EVENTOUT-Pad68)") (class "Default")
      (node (ref "U4") (pin "68") (pinfunction "PE15/FSMC_D12/TIM1_BKIN/EVENTOUT_68") (pintype "passive"))
    )
    (net (code "127") (name "unconnected-(U4B-PF0{slash}FSMC_A0{slash}I2C2_SDA{slash}EVENTOUT-Pad10)") (class "Default")
      (node (ref "U4") (pin "10") (pinfunction "PF0/FSMC_A0/I2C2_SDA/EVENTOUT_10") (pintype "passive"))
    )
    (net (code "128") (name "unconnected-(U4B-PF1{slash}FSMC_A1{slash}I2C2_SCL{slash}EVENTOUT-Pad11)") (class "Default")
      (node (ref "U4") (pin "11") (pinfunction "PF1/FSMC_A1/I2C2_SCL/EVENTOUT_11") (pintype "passive"))
    )
    (net (code "129") (name "unconnected-(U4B-PF2{slash}FSMC_A2{slash}I2C2_SMBA{slash}EVENTOUT-Pad12)") (class "Default")
      (node (ref "U4") (pin "12") (pinfunction "PF2/FSMC_A2/I2C2_SMBA/EVENTOUT_12") (pintype "passive"))
    )
    (net (code "130") (name "unconnected-(U4B-PF3{slash}FSMC_A3{slash}EVENTOUT{slash}ADC3_IN9-Pad13)") (class "Default")
      (node (ref "U4") (pin "13") (pinfunction "PF3/FSMC_A3/EVENTOUT/ADC3_IN9_13") (pintype "passive"))
    )
    (net (code "131") (name "unconnected-(U4B-PF4{slash}FSMC_A4{slash}EVENTOUT{slash}ADC3_IN14-Pad14)") (class "Default")
      (node (ref "U4") (pin "14") (pinfunction "PF4/FSMC_A4/EVENTOUT/ADC3_IN14_14") (pintype "passive"))
    )
    (net (code "132") (name "unconnected-(U4B-PF5{slash}FSMC_A5{slash}EVENTOUT{slash}ADC3_IN15-Pad15)") (class "Default")
      (node (ref "U4") (pin "15") (pinfunction "PF5/FSMC_A5/EVENTOUT/ADC3_IN15_15") (pintype "passive"))
    )
    (net (code "133") (name "unconnected-(U4B-PF6{slash}TIM10_CH1{slash}FSMC_NIORD{slash}EVENTOUT{slash}ADC3_IN4-Pad18)") (class "Default")
      (node (ref "U4") (pin "18") (pinfunction "PF6/TIM10_CH1/FSMC_NIORD/EVENTOUT/ADC3_IN4_18") (pintype "passive"))
    )
    (net (code "134") (name "unconnected-(U4B-PF7{slash}TIM11_CH1{slash}FSMC_NREG{slash}EVENTOUT{slash}ADC3_IN5-Pad19)") (class "Default")
      (node (ref "U4") (pin "19") (pinfunction "PF7/TIM11_CH1/FSMC_NREG/EVENTOUT/ADC3_IN5_19") (pintype "passive"))
    )
    (net (code "135") (name "unconnected-(U4B-PF8{slash}TIM13_CH1{slash}FSMC_NIOWR{slash}EVENTOUT{slash}ADC3_IN6-Pad20)") (class "Default")
      (node (ref "U4") (pin "20") (pinfunction "PF8/TIM13_CH1/FSMC_NIOWR/EVENTOUT/ADC3_IN6_20") (pintype "passive"))
    )
    (net (code "136") (name "unconnected-(U4B-PF9{slash}TIM14_CH1{slash}FSMC_CD{slash}EVENTOUT{slash}ADC3_IN7-Pad21)") (class "Default")
      (node (ref "U4") (pin "21") (pinfunction "PF9/TIM14_CH1/FSMC_CD/EVENTOUT/ADC3_IN7_21") (pintype "passive"))
    )
    (net (code "137") (name "unconnected-(U4B-PF10{slash}FSMC_INTR{slash}EVENTOUT{slash}ADC3_IN8-Pad22)") (class "Default")
      (node (ref "U4") (pin "22") (pinfunction "PF10/FSMC_INTR/EVENTOUT/ADC3_IN8_22") (pintype "passive"))
    )
    (net (code "138") (name "unconnected-(U4B-PF11{slash}DCMI_12{slash}EVENTOUT-Pad49)") (class "Default")
      (node (ref "U4") (pin "49") (pinfunction "PF11/DCMI_12/EVENTOUT_49") (pintype "passive"))
    )
    (net (code "139") (name "unconnected-(U4B-PF12{slash}FSMC_A6{slash}EVENTOUT-Pad50)") (class "Default")
      (node (ref "U4") (pin "50") (pinfunction "PF12/FSMC_A6/EVENTOUT_50") (pintype "passive"))
    )
    (net (code "140") (name "unconnected-(U4B-PF13{slash}FSMC_A7{slash}EVENTOUT-Pad53)") (class "Default")
      (node (ref "U4") (pin "53") (pinfunction "PF13/FSMC_A7/EVENTOUT_53") (pintype "passive"))
    )
    (net (code "141") (name "unconnected-(U4B-PF14{slash}FSMC_A8{slash}EVENTOUT-Pad54)") (class "Default")
      (node (ref "U4") (pin "54") (pinfunction "PF14/FSMC_A8/EVENTOUT_54") (pintype "passive"))
    )
    (net (code "142") (name "unconnected-(U4B-PF15{slash}FSMC_A9{slash}EVENTOUT-Pad55)") (class "Default")
      (node (ref "U4") (pin "55") (pinfunction "PF15/FSMC_A9/EVENTOUT_55") (pintype "passive"))
    )
    (net (code "143") (name "unconnected-(U4B-PG0{slash}FSMC_A10{slash}EVENTOUT-Pad56)") (class "Default")
      (node (ref "U4") (pin "56") (pinfunction "PG0/FSMC_A10/EVENTOUT_56") (pintype "passive"))
    )
    (net (code "144") (name "unconnected-(U4B-PG1{slash}FSMC_A11{slash}EVENTOUT-Pad57)") (class "Default")
      (node (ref "U4") (pin "57") (pinfunction "PG1/FSMC_A11/EVENTOUT_57") (pintype "passive"))
    )
    (net (code "145") (name "unconnected-(U4B-PG2{slash}FSMC_A12{slash}EVENTOUT-Pad87)") (class "Default")
      (node (ref "U4") (pin "87") (pinfunction "PG2/FSMC_A12/EVENTOUT_87") (pintype "passive"))
    )
    (net (code "146") (name "unconnected-(U4B-PG3{slash}FSMC_A13{slash}EVENTOUT-Pad88)") (class "Default")
      (node (ref "U4") (pin "88") (pinfunction "PG3/FSMC_A13/EVENTOUT_88") (pintype "passive"))
    )
    (net (code "147") (name "unconnected-(U4B-PG4{slash}FSMC_A14{slash}EVENTOUT-Pad89)") (class "Default")
      (node (ref "U4") (pin "89") (pinfunction "PG4/FSMC_A14/EVENTOUT_89") (pintype "passive"))
    )
    (net (code "148") (name "unconnected-(U4B-PG5{slash}FSMC_A15{slash}EVENTOUT-Pad90)") (class "Default")
      (node (ref "U4") (pin "90") (pinfunction "PG5/FSMC_A15/EVENTOUT_90") (pintype "passive"))
    )
    (net (code "149") (name "unconnected-(U4B-PG6{slash}FSMC_INT2{slash}EVENTOUT-Pad91)") (class "Default")
      (node (ref "U4") (pin "91") (pinfunction "PG6/FSMC_INT2/EVENTOUT_91") (pintype "passive"))
    )
    (net (code "150") (name "unconnected-(U4B-PG7{slash}FSMC_INT3{slash}USART6_CK{slash}EVENTOUT-Pad92)") (class "Default")
      (node (ref "U4") (pin "92") (pinfunction "PG7/FSMC_INT3/USART6_CK/EVENTOUT_92") (pintype "passive"))
    )
    (net (code "151") (name "unconnected-(U4B-PG8{slash}USART6_RTS{slash}ETH_PPS_OUT{slash}EVENTOUT-Pad93)") (class "Default")
      (node (ref "U4") (pin "93") (pinfunction "PG8/USART6_RTS/ETH_PPS_OUT/EVENTOUT_93") (pintype "passive"))
    )
    (net (code "152") (name "unconnected-(U4B-PG10{slash}FSMC_NCE4_1{slash}FSMC_NE3{slash}EVENTOUT-Pad125)") (class "Default")
      (node (ref "U4") (pin "125") (pinfunction "PG10/FSMC_NCE4_1/FSMC_NE3/EVENTOUT_125") (pintype "passive"))
    )
    (net (code "153") (name "unconnected-(U4B-PG12{slash}FSMC_NE4{slash}USART6_RTS{slash}EVENTOUT-Pad127)") (class "Default")
      (node (ref "U4") (pin "127") (pinfunction "PG12/FSMC_NE4/USART6_RTS/EVENTOUT_127") (pintype "passive"))
    )
    (net (code "154") (name "unconnected-(U4B-PG13{slash}FSMC_A24{slash}USART6_CTS{slash}ETH_MII_TXD0{slash}ETH_RMII_TXD0{slash}EVENTOUT-Pad128)") (class "Default")
      (node (ref "U4") (pin "128") (pinfunction "PG13/FSMC_A24/USART6_CTS/ETH_MII_TXD0/ETH_RMII_TXD0/EVENTOUT_128") (pintype "passive"))
    )
    (net (code "155") (name "unconnected-(U4B-PG15{slash}USART6_CTS{slash}DCMI_D13{slash}EVENTOUT-Pad132)") (class "Default")
      (node (ref "U4") (pin "132") (pinfunction "PG15/USART6_CTS/DCMI_D13/EVENTOUT_132") (pintype "passive"))
    )
    (net (code "156") (name "~{RESET}") (class "Default")
      (node (ref "C32") (pin "1") (pinfunction "1_1") (pintype "passive"))
      (node (ref "J7") (pin "5") (pinfunction "5_5") (pintype "passive"))
      (node (ref "R7") (pin "2") (pinfunction "2_2") (pintype "passive"))
      (node (ref "U4") (pin "25") (pinfunction "NRST_25") (pintype "passive"))
    )
  )
)
